# schematics.net
KiCad netlist of a schematic drawn in Altium Designer
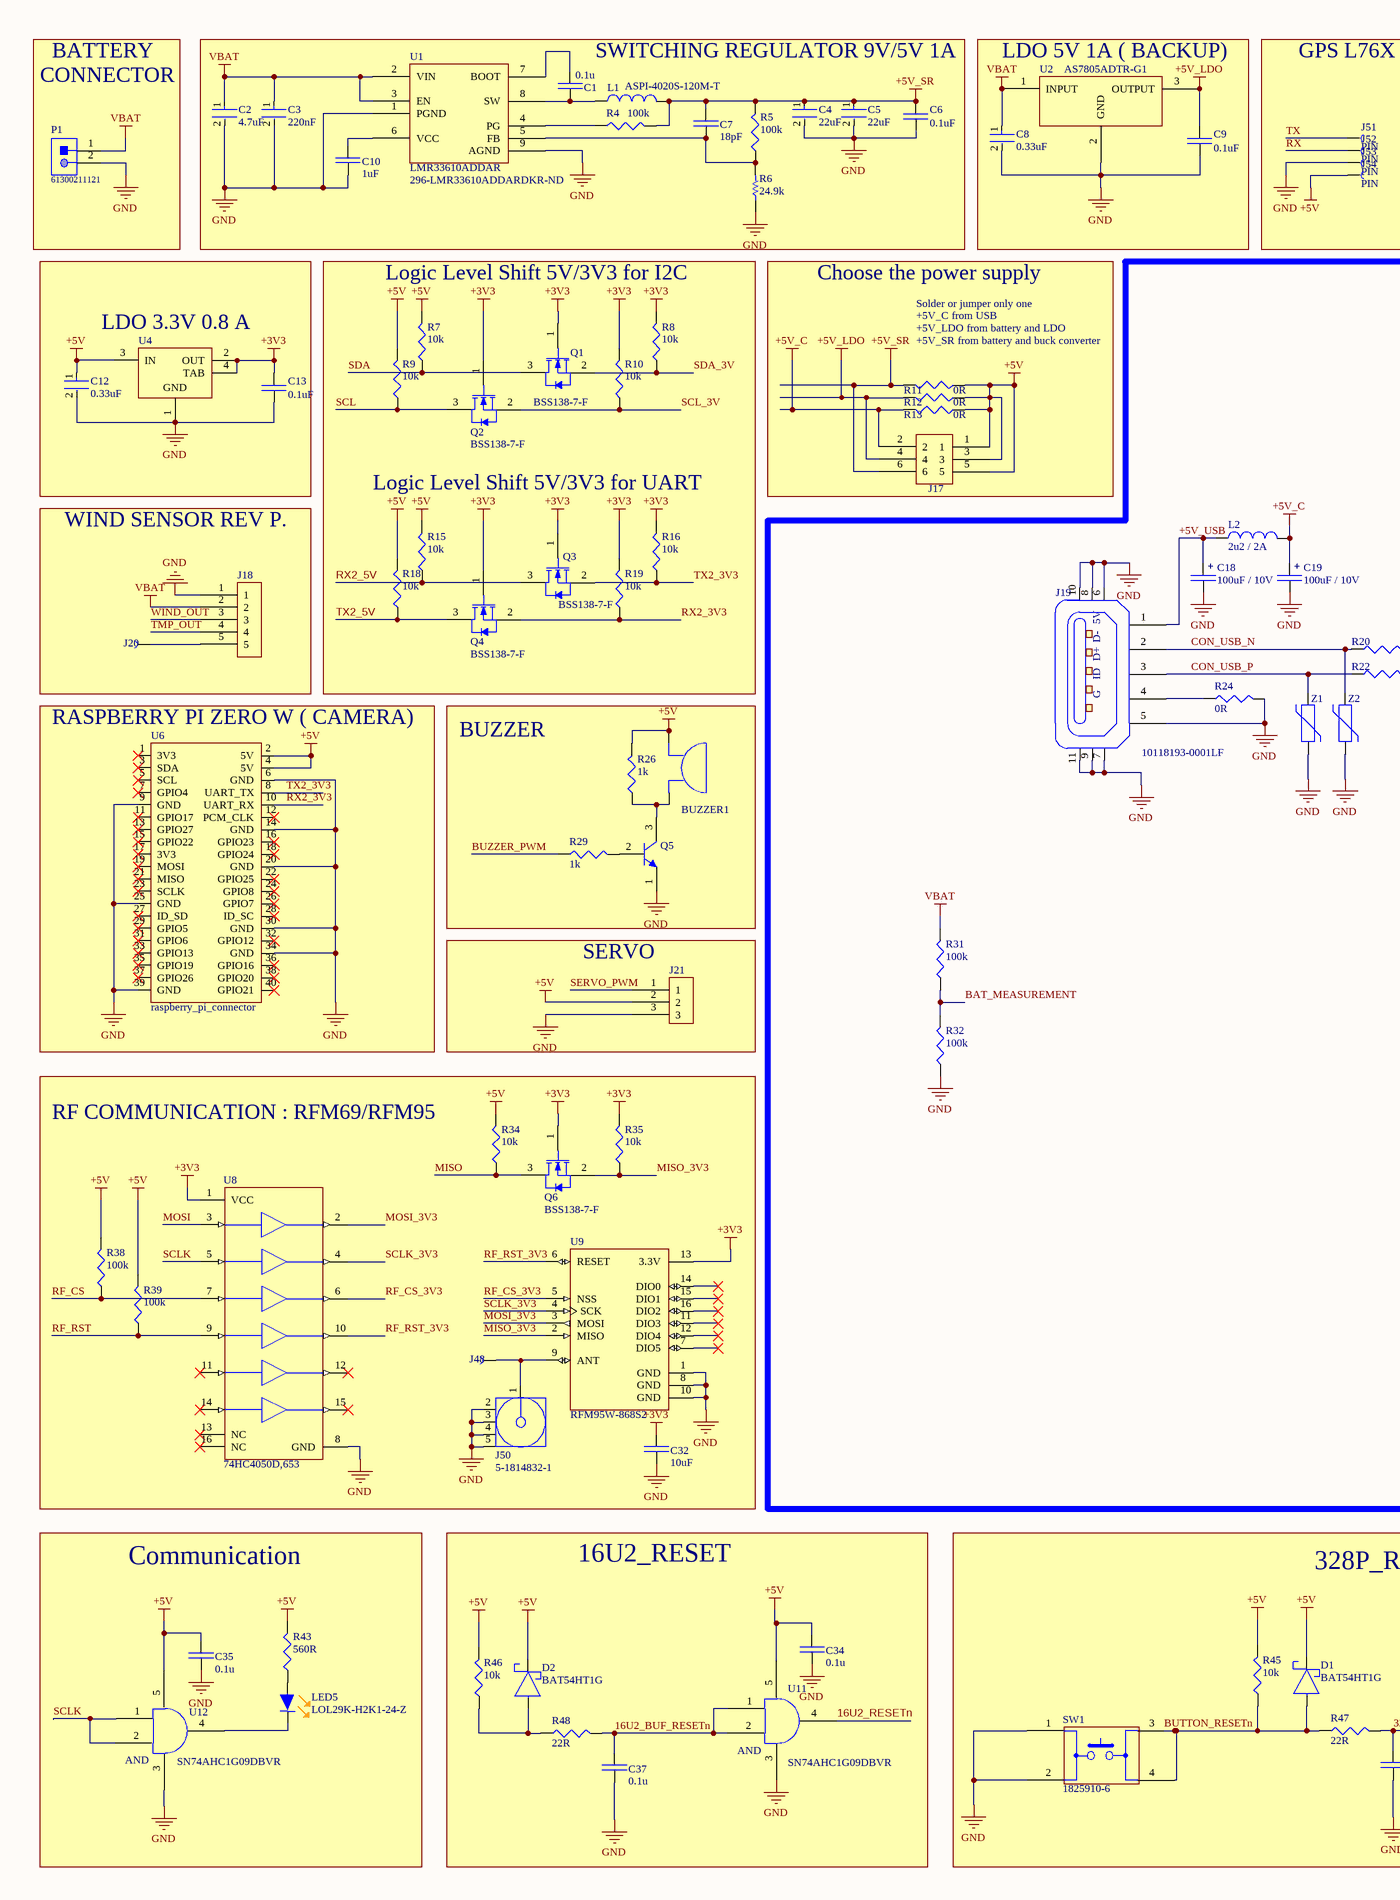
[diagram p0: schematics.SchDoc, left]
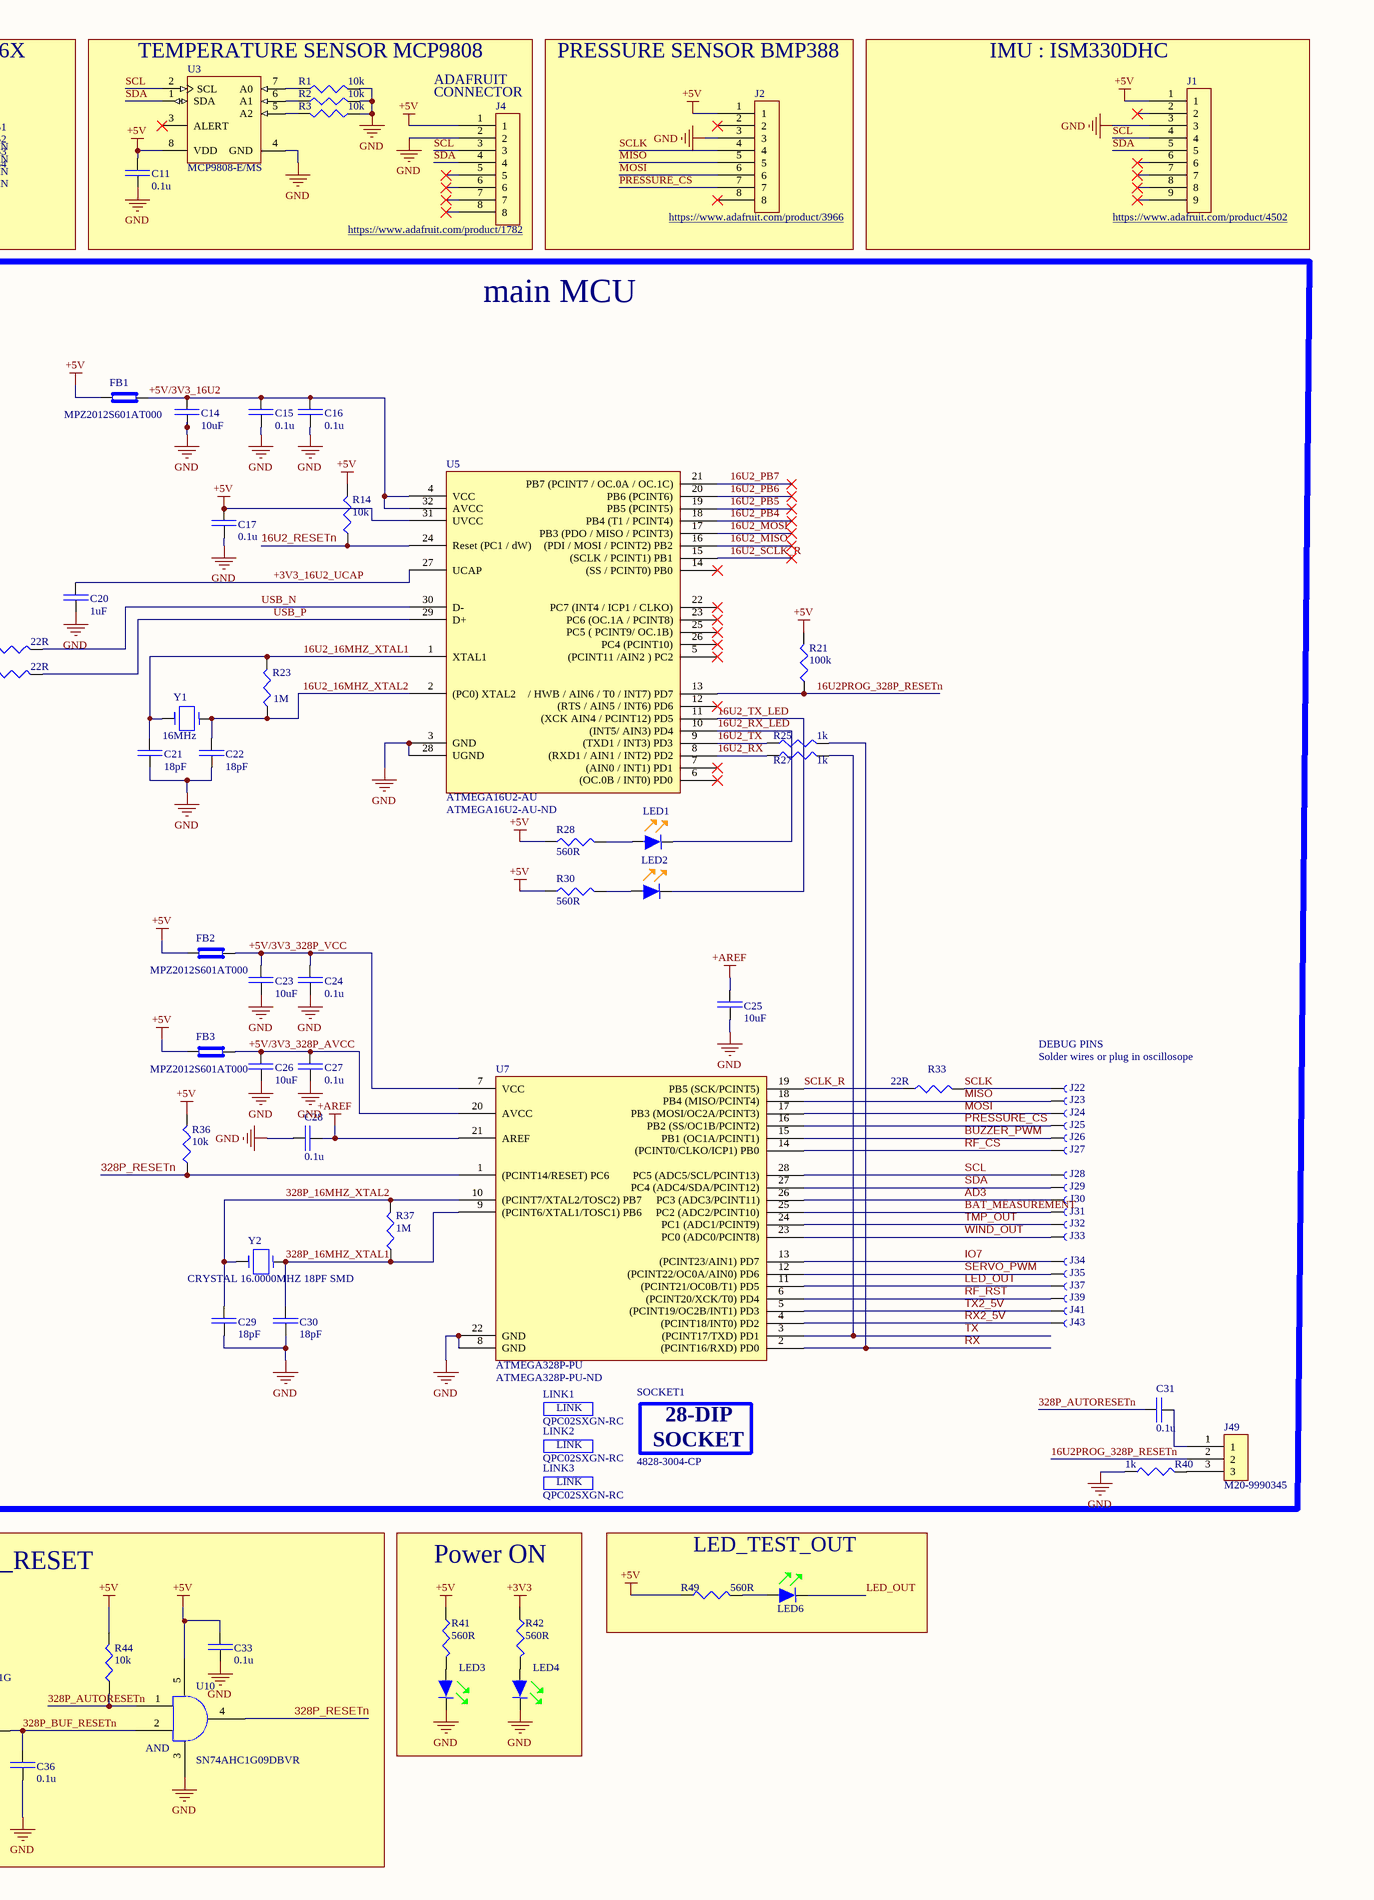
[diagram p1: schematics.SchDoc, right]

(export (version "E")
  (design (tool "Eeschema 10.0.6"))
  (components
    (comp (ref "BUZZER1")
      (value "PS1420P02CT")
      (footprint "PS1420P02CT")
      (description "AUDIO PIEZO TRANSDUCER 30V TH")
      (fields (field (name "MANUFACTURER") "TDK"))
      (libsource (lib "sch_library") (part "PS1420P02CT"))
    )
    (comp (ref "C1")
      (value "0.1u")
      (footprint "CAP_603")
      (description "CL10 Series 0603 0.1 uF 50 V ±10% Tolerance X7R Multilayer Ceramic Capacitor")
      (fields
        (field (name "MANUFACTURER") "Samsung")
        (field (name "MANUFACTURER PART NUMBER") "CL10B104KB8NNNL")
      )
      (libsource (lib "sch_library") (part "CL10B104KB8NNNL"))
    )
    (comp (ref "C2")
      (value "4.7uF")
      (footprint "FP-CL21-IPC_B")
      (description "CL21 Series 0805 4.7uF 25V ±10% Tolerance X5R Multilayer Ceramic Chip Capacitor")
      (fields (field (name "TOLERANCE") "10%") (field (name "VOLTAGE") "25V"))
      (libsource (lib "Altium Content Vault") (part "b4654b650e69147ec39a6b967a45e02"))
    )
    (comp (ref "C3")
      (value "220nF")
      (footprint "FP-CC0603-DA-MFG")
      (description "0603 0.22 uF 16 V ±10 % Tolerance X7R SMT Multilayer Ceramic Capacitor")
      (fields
        (field (name "MANUFACTURER") "YAGEO")
        (field (name "OCTOPART") "https://octopart.com/cc0603krx7r7bb224-yageo-6827757")
      )
      (libsource (lib "Altium Content Vault") (part "11868f565c42a9108669ba33697ecf6"))
    )
    (comp (ref "C4")
      (value "22uF")
      (footprint "FP-CL31-IPC_A")
      (description "Cap Ceramic 22uF 16V X5R ±20% SMD 1206 +85°C Embossed T/R")
      (fields (field (name "TOLERANCE") "20%") (field (name "VOLTAGE") "16V"))
      (libsource (lib "Altium Content Vault") (part "b4654b650e69147ec39a6b967a45e02"))
    )
    (comp (ref "C5")
      (value "22uF")
      (footprint "FP-CL31-IPC_A")
      (description "Cap Ceramic 22uF 16V X5R ±20% SMD 1206 +85°C Embossed T/R")
      (fields (field (name "TOLERANCE") "20%") (field (name "VOLTAGE") "16V"))
      (libsource (lib "Altium Content Vault") (part "b4654b650e69147ec39a6b967a45e02"))
    )
    (comp (ref "C6")
      (value "0.1uF")
      (footprint "CAP_603")
      (description "CL10 Series 0603 0.1 uF 50 V ±10% Tolerance X7R Multilayer Ceramic Capacitor")
      (fields
        (field (name "MANUFACTURER") "Samsung")
        (field (name "MANUFACTURER PART NUMBER") "CL10B104KB8NNNL")
      )
      (libsource (lib "sch_library") (part "CL10B104KB8NNNL"))
    )
    (comp (ref "C7")
      (value "18pF")
      (footprint "CAP_603")
      (description "0603 18 pF 50V ±5% Tolerance C0G/NP0 Surface Mount Multilayer Ceramic Capacitor")
      (fields
        (field (name "MANUFACTURER") "Kyocera AVX")
        (field (name "MANUFACTURER PART NUMBER") "06035A180JAT2A")
      )
      (libsource (lib "sch_library") (part "06035A180JAT2A"))
    )
    (comp (ref "C8")
      (value "0.33uF")
      (footprint "FP-CL21-F-IPC_C")
      (description "CAP CER 0.33UF 50V X7R 0805")
      (fields
        (field (name "MANUFACTURER") "Samsung Electro-Mechanics")
        (field (name "OCTOPART") "https://octopart.com/cl21b334kbfnnne-samsung-9287149")
      )
      (libsource (lib "Altium Content Vault") (part "11868f565c42a9108669ba33697ecf6"))
    )
    (comp (ref "C9")
      (value "0.1uF")
      (footprint "CAP_603")
      (description "CL10 Series 0603 0.1 uF 50 V ±10% Tolerance X7R Multilayer Ceramic Capacitor")
      (fields
        (field (name "MANUFACTURER") "Samsung")
        (field (name "MANUFACTURER PART NUMBER") "CL10B104KB8NNNL")
      )
      (libsource (lib "sch_library") (part "CL10B104KB8NNNL"))
    )
    (comp (ref "C10")
      (value "1uF")
      (footprint "CAP_603")
      (fields
        (field (name "MANUFACTURER") "Yageo")
        (field (name "MANUFACTURER PART NUMBER") "CC0603KRX5R8BB105")
        (field (name "TOLERANCE") "10%")
      )
      (libsource (lib "sch_library") (part "CC0603KRX5R8BB105"))
    )
    (comp (ref "C11")
      (value "0.1u")
      (footprint "CAP_603")
      (description "CL10 Series 0603 0.1 uF 50 V ±10% Tolerance X7R Multilayer Ceramic Capacitor")
      (fields
        (field (name "MANUFACTURER") "Samsung")
        (field (name "MANUFACTURER PART NUMBER") "CL10B104KB8NNNL")
      )
      (libsource (lib "sch_library") (part "CL10B104KB8NNNL"))
    )
    (comp (ref "C12")
      (value "0.33uF")
      (footprint "FP-CL21-F-IPC_C")
      (description "CAP CER 0.33UF 50V X7R 0805")
      (fields
        (field (name "MANUFACTURER") "Samsung Electro-Mechanics")
        (field (name "OCTOPART") "https://octopart.com/cl21b334kbfnnne-samsung-9287149")
      )
      (libsource (lib "Altium Content Vault") (part "11868f565c42a9108669ba33697ecf6"))
    )
    (comp (ref "C13")
      (value "0.1uF")
      (footprint "CAP_603")
      (description "CL10 Series 0603 0.1 uF 50 V ±10% Tolerance X7R Multilayer Ceramic Capacitor")
      (fields
        (field (name "MANUFACTURER") "Samsung")
        (field (name "MANUFACTURER PART NUMBER") "CL10B104KB8NNNL")
      )
      (libsource (lib "sch_library") (part "CL10B104KB8NNNL"))
    )
    (comp (ref "C14")
      (value "10uF")
      (footprint "CAP_0805")
      (description "Ceramic capacitor SMD 0805 10 µF 16 V 10 %")
      (fields
        (field (name "MANUFACTURER") "Samsung")
        (field (name "MANUFACTURER PART NUMBER") "CL21A106KOQNNNG")
      )
      (libsource (lib "sch_library") (part "CL21A106KOQNNNG"))
    )
    (comp (ref "C15")
      (value "0.1u")
      (footprint "CAP_603")
      (description "CL10 Series 0603 0.1 uF 50 V ±10% Tolerance X7R Multilayer Ceramic Capacitor")
      (fields
        (field (name "MANUFACTURER") "Samsung")
        (field (name "MANUFACTURER PART NUMBER") "CL10B104KB8NNNL")
      )
      (libsource (lib "sch_library") (part "CL10B104KB8NNNL"))
    )
    (comp (ref "C16")
      (value "0.1u")
      (footprint "CAP_603")
      (description "CL10 Series 0603 0.1 uF 50 V ±10% Tolerance X7R Multilayer Ceramic Capacitor")
      (fields
        (field (name "MANUFACTURER") "Samsung")
        (field (name "MANUFACTURER PART NUMBER") "CL10B104KB8NNNL")
      )
      (libsource (lib "sch_library") (part "CL10B104KB8NNNL"))
    )
    (comp (ref "C17")
      (value "0.1u")
      (footprint "CAP_603")
      (description "CL10 Series 0603 0.1 uF 50 V ±10% Tolerance X7R Multilayer Ceramic Capacitor")
      (fields
        (field (name "MANUFACTURER") "Samsung")
        (field (name "MANUFACTURER PART NUMBER") "CL10B104KB8NNNL")
      )
      (libsource (lib "sch_library") (part "CL10B104KB8NNNL"))
    )
    (comp (ref "C18")
      (value "100uF / 10V")
      (footprint "EEE-1AA101WR")
      (description "Cap Aluminum 100uF 10V 20% (5 X 5.4mm) SMD 50mA 1000 hr 85°C T/R")
      (fields
        (field (name "MANUFACTURER") "Panasonic")
        (field (name "MANUFACTURER PART NUMBER") "EEE-1AA101WR")
      )
      (libsource (lib "sch_library") (part "EEE-1AA101WR"))
    )
    (comp (ref "C19")
      (value "100uF / 10V")
      (footprint "EEE-1AA101WR")
      (description "Cap Aluminum 100uF 10V 20% (5 X 5.4mm) SMD 50mA 1000 hr 85°C T/R")
      (fields
        (field (name "MANUFACTURER") "Panasonic")
        (field (name "MANUFACTURER PART NUMBER") "EEE-1AA101WR")
      )
      (libsource (lib "sch_library") (part "EEE-1AA101WR"))
    )
    (comp (ref "C20")
      (value "1uF")
      (footprint "CAP_603")
      (fields
        (field (name "MANUFACTURER") "Yageo")
        (field (name "MANUFACTURER PART NUMBER") "CC0603KRX5R8BB105")
        (field (name "TOLERANCE") "10%")
      )
      (libsource (lib "sch_library") (part "CC0603KRX5R8BB105"))
    )
    (comp (ref "C21")
      (value "18pF")
      (footprint "CAP_603")
      (description "0603 18 pF 50V ±5% Tolerance C0G/NP0 Surface Mount Multilayer Ceramic Capacitor")
      (fields
        (field (name "MANUFACTURER") "Kyocera AVX")
        (field (name "MANUFACTURER PART NUMBER") "06035A180JAT2A")
      )
      (libsource (lib "sch_library") (part "06035A180JAT2A"))
    )
    (comp (ref "C22")
      (value "18pF")
      (footprint "CAP_603")
      (description "0603 18 pF 50V ±5% Tolerance C0G/NP0 Surface Mount Multilayer Ceramic Capacitor")
      (fields
        (field (name "MANUFACTURER") "Kyocera AVX")
        (field (name "MANUFACTURER PART NUMBER") "06035A180JAT2A")
      )
      (libsource (lib "sch_library") (part "06035A180JAT2A"))
    )
    (comp (ref "C23")
      (value "10uF")
      (footprint "CAP_0805")
      (description "Ceramic capacitor SMD 0805 10 µF 16 V 10 %")
      (fields
        (field (name "MANUFACTURER") "Samsung")
        (field (name "MANUFACTURER PART NUMBER") "CL21A106KOQNNNG")
      )
      (libsource (lib "sch_library") (part "CL21A106KOQNNNG"))
    )
    (comp (ref "C24")
      (value "0.1u")
      (footprint "CAP_603")
      (description "CL10 Series 0603 0.1 uF 50 V ±10% Tolerance X7R Multilayer Ceramic Capacitor")
      (fields
        (field (name "MANUFACTURER") "Samsung")
        (field (name "MANUFACTURER PART NUMBER") "CL10B104KB8NNNL")
      )
      (libsource (lib "sch_library") (part "CL10B104KB8NNNL"))
    )
    (comp (ref "C25")
      (value "10uF")
      (footprint "CAP_0805")
      (description "Ceramic capacitor SMD 0805 10 µF 16 V 10 %")
      (fields
        (field (name "MANUFACTURER") "Samsung")
        (field (name "MANUFACTURER PART NUMBER") "CL21A106KOQNNNG")
      )
      (libsource (lib "sch_library") (part "CL21A106KOQNNNG"))
    )
    (comp (ref "C26")
      (value "10uF")
      (footprint "CAP_0805")
      (description "Ceramic capacitor SMD 0805 10 µF 16 V 10 %")
      (fields
        (field (name "MANUFACTURER") "Samsung")
        (field (name "MANUFACTURER PART NUMBER") "CL21A106KOQNNNG")
      )
      (libsource (lib "sch_library") (part "CL21A106KOQNNNG"))
    )
    (comp (ref "C27")
      (value "0.1u")
      (footprint "CAP_603")
      (description "CL10 Series 0603 0.1 uF 50 V ±10% Tolerance X7R Multilayer Ceramic Capacitor")
      (fields
        (field (name "MANUFACTURER") "Samsung")
        (field (name "MANUFACTURER PART NUMBER") "CL10B104KB8NNNL")
      )
      (libsource (lib "sch_library") (part "CL10B104KB8NNNL"))
    )
    (comp (ref "C28")
      (value "0.1u")
      (footprint "CAP_603")
      (description "CL10 Series 0603 0.1 uF 50 V ±10% Tolerance X7R Multilayer Ceramic Capacitor")
      (fields
        (field (name "MANUFACTURER") "Samsung")
        (field (name "MANUFACTURER PART NUMBER") "CL10B104KB8NNNL")
      )
      (libsource (lib "sch_library") (part "CL10B104KB8NNNL"))
    )
    (comp (ref "C29")
      (value "18pF")
      (footprint "CAP_603")
      (description "0603 18 pF 50V ±5% Tolerance C0G/NP0 Surface Mount Multilayer Ceramic Capacitor")
      (fields
        (field (name "MANUFACTURER") "Kyocera AVX")
        (field (name "MANUFACTURER PART NUMBER") "06035A180JAT2A")
      )
      (libsource (lib "sch_library") (part "06035A180JAT2A"))
    )
    (comp (ref "C30")
      (value "18pF")
      (footprint "CAP_603")
      (description "0603 18 pF 50V ±5% Tolerance C0G/NP0 Surface Mount Multilayer Ceramic Capacitor")
      (fields
        (field (name "MANUFACTURER") "Kyocera AVX")
        (field (name "MANUFACTURER PART NUMBER") "06035A180JAT2A")
      )
      (libsource (lib "sch_library") (part "06035A180JAT2A"))
    )
    (comp (ref "C31")
      (value "0.1u")
      (footprint "CAP_603")
      (description "CL10 Series 0603 0.1 uF 50 V ±10% Tolerance X7R Multilayer Ceramic Capacitor")
      (fields
        (field (name "MANUFACTURER") "Samsung")
        (field (name "MANUFACTURER PART NUMBER") "CL10B104KB8NNNL")
      )
      (libsource (lib "sch_library") (part "CL10B104KB8NNNL"))
    )
    (comp (ref "C32")
      (value "10uF")
      (footprint "CAP_0805")
      (description "Ceramic capacitor SMD 0805 10 µF 16 V 10 %")
      (fields
        (field (name "MANUFACTURER") "Samsung")
        (field (name "MANUFACTURER PART NUMBER") "CL21A106KOQNNNG")
      )
      (libsource (lib "sch_library") (part "CL21A106KOQNNNG"))
    )
    (comp (ref "C33")
      (value "0.1u")
      (footprint "CAP_603")
      (description "CL10 Series 0603 0.1 uF 50 V ±10% Tolerance X7R Multilayer Ceramic Capacitor")
      (fields
        (field (name "MANUFACTURER") "Samsung")
        (field (name "MANUFACTURER PART NUMBER") "CL10B104KB8NNNL")
      )
      (libsource (lib "sch_library") (part "CL10B104KB8NNNL"))
    )
    (comp (ref "C34")
      (value "0.1u")
      (footprint "CAP_603")
      (description "CL10 Series 0603 0.1 uF 50 V ±10% Tolerance X7R Multilayer Ceramic Capacitor")
      (fields
        (field (name "MANUFACTURER") "Samsung")
        (field (name "MANUFACTURER PART NUMBER") "CL10B104KB8NNNL")
      )
      (libsource (lib "sch_library") (part "CL10B104KB8NNNL"))
    )
    (comp (ref "C35")
      (value "0.1u")
      (footprint "CAP_603")
      (description "CL10 Series 0603 0.1 uF 50 V ±10% Tolerance X7R Multilayer Ceramic Capacitor")
      (fields
        (field (name "MANUFACTURER") "Samsung")
        (field (name "MANUFACTURER PART NUMBER") "CL10B104KB8NNNL")
      )
      (libsource (lib "sch_library") (part "CL10B104KB8NNNL"))
    )
    (comp (ref "C36")
      (value "0.1u")
      (footprint "CAP_603")
      (description "CL10 Series 0603 0.1 uF 50 V ±10% Tolerance X7R Multilayer Ceramic Capacitor")
      (fields
        (field (name "MANUFACTURER") "Samsung")
        (field (name "MANUFACTURER PART NUMBER") "CL10B104KB8NNNL")
      )
      (libsource (lib "sch_library") (part "CL10B104KB8NNNL"))
    )
    (comp (ref "C37")
      (value "0.1u")
      (footprint "CAP_603")
      (description "CL10 Series 0603 0.1 uF 50 V ±10% Tolerance X7R Multilayer Ceramic Capacitor")
      (fields
        (field (name "MANUFACTURER") "Samsung")
        (field (name "MANUFACTURER PART NUMBER") "CL10B104KB8NNNL")
      )
      (libsource (lib "sch_library") (part "CL10B104KB8NNNL"))
    )
    (comp (ref "D1")
      (value "BAT54HT1G")
      (footprint "BAT54HT1G")
      (description "Small Signal Schottky Diode, Single, 30 V, 200 mA, 800 mV, 600 mA, 150 C ;RoHS Compliant: Yes")
      (fields (field (name "MANUFACTURER") "ON Semiconductor / Fairchild"))
      (libsource (lib "sch_library") (part "BAT54HT1G"))
    )
    (comp (ref "D2")
      (value "BAT54HT1G")
      (footprint "BAT54HT1G")
      (description "Small Signal Schottky Diode, Single, 30 V, 200 mA, 800 mV, 600 mA, 150 C ;RoHS Compliant: Yes")
      (fields (field (name "MANUFACTURER") "ON Semiconductor / Fairchild"))
      (libsource (lib "sch_library") (part "BAT54HT1G"))
    )
    (comp (ref "FB1")
      (value "MPZ2012S601AT000")
      (footprint "FB_0805")
      (description "FERRITE BEAD 600 OHM 0805 1LN")
      (fields (field (name "MANUFACTURER") "TDK"))
      (libsource (lib "sch_library") (part "MPZ2012S601AT000"))
    )
    (comp (ref "FB2")
      (value "MPZ2012S601AT000")
      (footprint "FB_0805")
      (description "FERRITE BEAD 600 OHM 0805 1LN")
      (fields (field (name "MANUFACTURER") "TDK"))
      (libsource (lib "sch_library") (part "MPZ2012S601AT000"))
    )
    (comp (ref "FB3")
      (value "MPZ2012S601AT000")
      (footprint "FB_0805")
      (description "FERRITE BEAD 600 OHM 0805 1LN")
      (fields (field (name "MANUFACTURER") "TDK"))
      (libsource (lib "sch_library") (part "MPZ2012S601AT000"))
    )
    (comp (ref "J1")
      (value "https://www.adafruit.com/product/4502")
      (footprint "ISM330DHCX_adafruit")
      (description "https://www.adafruit.com/product/4502#technical-details")
      (libsource (lib "sch_library") (part "ISM330DHCX_adafruit"))
    )
    (comp (ref "J2")
      (value "https://www.adafruit.com/product/3966")
      (footprint "BMP388_adafruit")
      (fields (field (name "MANUFACTURER") "Harwin") (field (name "MANUFACTURER PART NUMBER") "M20-7820842"))
      (libsource (lib "sch_library") (part "BMP388_adafruit"))
    )
    (comp (ref "J4")
      (value "https://www.adafruit.com/product/1782")
      (footprint "MCP9808_adafruit")
      (libsource (lib "sch_library") (part "MCP9808_adafruit"))
    )
    (comp (ref "J17")
      (value "M20-9760346")
      (footprint "HEADER_MALE_2x3PIN")
      (description "03+03 DIL VERT PIN HDR")
      (fields (field (name "MANUFACTURER") "Harwin"))
      (libsource (lib "sch_library") (part "M20-9760346"))
    )
    (comp (ref "J18")
      (value "M20-9990546 (3)")
      (footprint "HEADER_MALE_1X5")
      (description "HEADER, 1ROW, 5WAY")
      (fields (field (name "MANUFACTURER") "Harwin") (field (name "MANUFACTURER PART NUMBER") "M20-9990546"))
      (libsource (lib "sch_library") (part "M20-9990546 (3)"))
    )
    (comp (ref "J19")
      (value "10118193-0001LF")
      (footprint "10118193-0001LF")
      (description "CONN USB MICRO B RECPT SMT R/A")
      (fields (field (name "MANUFACTURER") "Amphenol FCI"))
      (libsource (lib "sch_library") (part "10118193-0001LF"))
    )
    (comp (ref "J20") (value "PIN") (footprint "PIN") (libsource (lib "sch_library") (part "PIN")))
    (comp (ref "J21")
      (value "M20-9990345")
      (footprint "HEADER_MALE_1x3")
      (fields (field (name "MANUFACTURER") "Harwin"))
      (libsource (lib "sch_library") (part "M20-9990345"))
    )
    (comp (ref "J22") (value "PIN") (footprint "PIN") (libsource (lib "sch_library") (part "PIN")))
    (comp (ref "J23") (value "PIN") (footprint "PIN") (libsource (lib "sch_library") (part "PIN")))
    (comp (ref "J24") (value "PIN") (footprint "PIN") (libsource (lib "sch_library") (part "PIN")))
    (comp (ref "J25") (value "PIN") (footprint "PIN") (libsource (lib "sch_library") (part "PIN")))
    (comp (ref "J26") (value "PIN") (footprint "PIN") (libsource (lib "sch_library") (part "PIN")))
    (comp (ref "J27") (value "PIN") (footprint "PIN") (libsource (lib "sch_library") (part "PIN")))
    (comp (ref "J28") (value "PIN") (footprint "PIN") (libsource (lib "sch_library") (part "PIN")))
    (comp (ref "J29") (value "PIN") (footprint "PIN") (libsource (lib "sch_library") (part "PIN")))
    (comp (ref "J30") (value "PIN") (footprint "PIN") (libsource (lib "sch_library") (part "PIN")))
    (comp (ref "J31") (value "PIN") (footprint "PIN") (libsource (lib "sch_library") (part "PIN")))
    (comp (ref "J32") (value "PIN") (footprint "PIN") (libsource (lib "sch_library") (part "PIN")))
    (comp (ref "J33") (value "PIN") (footprint "PIN") (libsource (lib "sch_library") (part "PIN")))
    (comp (ref "J34") (value "PIN") (footprint "PIN") (libsource (lib "sch_library") (part "PIN")))
    (comp (ref "J35") (value "PIN") (footprint "PIN") (libsource (lib "sch_library") (part "PIN")))
    (comp (ref "J37") (value "PIN") (footprint "PIN") (libsource (lib "sch_library") (part "PIN")))
    (comp (ref "J39") (value "PIN") (footprint "PIN") (libsource (lib "sch_library") (part "PIN")))
    (comp (ref "J41") (value "PIN") (footprint "PIN") (libsource (lib "sch_library") (part "PIN")))
    (comp (ref "J43") (value "PIN") (footprint "PIN") (libsource (lib "sch_library") (part "PIN")))
    (comp (ref "J48") (value "PIN") (footprint "PIN") (libsource (lib "sch_library") (part "PIN")))
    (comp (ref "J49")
      (value "M20-9990345")
      (footprint "HEADER_MALE_1x3")
      (fields (field (name "MANUFACTURER") "Harwin"))
      (libsource (lib "sch_library") (part "M20-9990345"))
    )
    (comp (ref "J50")
      (value "5-1814832-1")
      (footprint "TECO-5-1814832-1_V")
      (fields (field (name "MANUFACTURER") "TE Connectivity"))
      (libsource (lib "Altium Content Vault") (part "CN-S-4F-RF5"))
    )
    (comp (ref "J51") (value "PIN") (footprint "PIN") (libsource (lib "sch_library") (part "PIN")))
    (comp (ref "J52") (value "PIN") (footprint "PIN") (libsource (lib "sch_library") (part "PIN")))
    (comp (ref "J53") (value "PIN") (footprint "PIN") (libsource (lib "sch_library") (part "PIN")))
    (comp (ref "J54") (value "PIN") (footprint "PIN") (libsource (lib "sch_library") (part "PIN")))
    (comp (ref "L1")
      (value "ASPI-4020S-120M-T")
      (footprint "ASPI-4020S")
      (description "Ind Power Shielded Wirewound 12uH 20% 100KHz Ferrite 880mA 1616 T/R")
      (fields (field (name "MANUFACTURER") "Abracon") (field (name "TOLERANCE") "20%"))
      (libsource (lib "sch_library") (part "ASPI-4020S-120M-T"))
    )
    (comp (ref "L2")
      (value "2u2 / 2A")
      (footprint "L_1210")
      (description "FIXED IND 2.2UH 2A 80 MOHM SMD")
      (fields
        (field (name "MANUFACTURER") "KEMET")
        (field (name "MANUFACTURER PART NUMBER") "L1210R2R2MDWIT")
      )
      (libsource (lib "sch_library") (part "L1210R2R2MDWIT"))
    )
    (comp (ref "LED1")
      (value "LOL29K-H2K1-24-Z")
      (footprint "LED_0603")
      (description "OSRAM - LO L29K-H2K1-24-Z - SMARTLED 0603 ORANGE")
      (fields (field (name "MANUFACTURER") "Osram Opto"))
      (libsource (lib "sch_library") (part "LOL29K-H2K1-24-Z"))
    )
    (comp (ref "LED2")
      (value "LOL29K-H2K1-24-Z")
      (footprint "LED_0603")
      (description "OSRAM - LO L29K-H2K1-24-Z - SMARTLED 0603 ORANGE")
      (fields (field (name "MANUFACTURER") "Osram Opto"))
      (libsource (lib "sch_library") (part "LOL29K-H2K1-24-Z"))
    )
    (comp (ref "LED3")
      (value "LGL29K-F2J1-24-Z")
      (footprint "LED_0603")
      (description "LED Uni-Color Green 572nm Automotive 2-Pin Chip 0603(1608Metric) T/R")
      (fields (field (name "MANUFACTURER") "Osram Opto"))
      (libsource (lib "sch_library") (part "LGL29K-F2J1-24-Z"))
    )
    (comp (ref "LED4")
      (value "LGL29K-F2J1-24-Z")
      (footprint "LED_0603")
      (description "LED Uni-Color Green 572nm Automotive 2-Pin Chip 0603(1608Metric) T/R")
      (fields (field (name "MANUFACTURER") "Osram Opto"))
      (libsource (lib "sch_library") (part "LGL29K-F2J1-24-Z"))
    )
    (comp (ref "LED5")
      (value "LOL29K-H2K1-24-Z")
      (footprint "LED_0603")
      (description "OSRAM - LO L29K-H2K1-24-Z - SMARTLED 0603 ORANGE")
      (fields (field (name "MANUFACTURER") "Osram Opto"))
      (libsource (lib "sch_library") (part "LOL29K-H2K1-24-Z"))
    )
    (comp (ref "LED6")
      (value "LGL29K-F2J1-24-Z")
      (footprint "LED_0603")
      (description "LED Uni-Color Green 572nm Automotive 2-Pin Chip 0603(1608Metric) T/R")
      (fields (field (name "MANUFACTURER") "Osram Opto"))
      (libsource (lib "sch_library") (part "LGL29K-F2J1-24-Z"))
    )
    (comp (ref "LINK1")
      (value "QPC02SXGN-RC")
      (description "CONN JUMPER SHORTING .100\" GOLD")
      (fields (field (name "MANUFACTURER") "Sullins"))
      (libsource (lib "sch_library") (part "QPC02SXGN-RC"))
    )
    (comp (ref "LINK2")
      (value "QPC02SXGN-RC")
      (description "CONN JUMPER SHORTING .100\" GOLD")
      (fields (field (name "MANUFACTURER") "Sullins"))
      (libsource (lib "sch_library") (part "QPC02SXGN-RC"))
    )
    (comp (ref "LINK3")
      (value "QPC02SXGN-RC")
      (description "CONN JUMPER SHORTING .100\" GOLD")
      (fields (field (name "MANUFACTURER") "Sullins"))
      (libsource (lib "sch_library") (part "QPC02SXGN-RC"))
    )
    (comp (ref "P1")
      (value "61300211121")
      (footprint "61300211121")
      (description "THT Vertical Pin Header WR-PHD, Pitch 2.54 mm, Single Row, 2 pins")
      (fields (field (name "MANUFACTURER") "Wurth Elektronik") (field (name "PUBLISHER") "WurthElektronik"))
      (libsource (lib "Altium Content Vault") (part "WE-CN-1P-M-R2"))
    )
    (comp (ref "Q1")
      (value "BSS138-7-F")
      (footprint "DIOD-SOT23-3_V")
      (description "N-Channel Enhancement Mode Mosfet, 50 V, 0.2 A, -55 to 150 degC, 3-Pin SOT23, RoHS, Tape and Reel")
      (fields (field (name "MANUFACTURER") "Diodes Inc"))
      (libsource (lib "Altium Content Vault") (part "NEMOS-GSD-3"))
    )
    (comp (ref "Q2")
      (value "BSS138-7-F")
      (footprint "DIOD-SOT23-3_V")
      (description "N-Channel Enhancement Mode Mosfet, 50 V, 0.2 A, -55 to 150 degC, 3-Pin SOT23, RoHS, Tape and Reel")
      (fields (field (name "MANUFACTURER") "Diodes Inc"))
      (libsource (lib "Altium Content Vault") (part "NEMOS-GSD-3"))
    )
    (comp (ref "Q3")
      (value "BSS138-7-F")
      (footprint "DIOD-SOT23-3_V")
      (description "N-Channel Enhancement Mode Mosfet, 50 V, 0.2 A, -55 to 150 degC, 3-Pin SOT23, RoHS, Tape and Reel")
      (fields (field (name "MANUFACTURER") "Diodes Inc"))
      (libsource (lib "Altium Content Vault") (part "NEMOS-GSD-3"))
    )
    (comp (ref "Q4")
      (value "BSS138-7-F")
      (footprint "DIOD-SOT23-3_V")
      (description "N-Channel Enhancement Mode Mosfet, 50 V, 0.2 A, -55 to 150 degC, 3-Pin SOT23, RoHS, Tape and Reel")
      (fields (field (name "MANUFACTURER") "Diodes Inc"))
      (libsource (lib "Altium Content Vault") (part "NEMOS-GSD-3"))
    )
    (comp (ref "Q5")
      (value "2SC2412KT146R")
      (footprint "ROHM-SOT-346-3_V")
      (fields (field (name "MANUFACTURER") "Rohm"))
      (libsource (lib "Altium Content Vault") (part "BJT-NPN-EBC-3"))
    )
    (comp (ref "Q6")
      (value "BSS138-7-F")
      (footprint "DIOD-SOT23-3_V")
      (description "N-Channel Enhancement Mode Mosfet, 50 V, 0.2 A, -55 to 150 degC, 3-Pin SOT23, RoHS, Tape and Reel")
      (fields (field (name "MANUFACTURER") "Diodes Inc"))
      (libsource (lib "Altium Content Vault") (part "NEMOS-GSD-3"))
    )
    (comp (ref "R1")
      (value "10k")
      (footprint "R_0603")
      (description "RES SMD 10K OHM 1% 1/10W 0603")
      (fields
        (field (name "MANUFACTURER") "Yageo")
        (field (name "MANUFACTURER PART NUMBER") "AC0603FR-0710KL")
      )
      (libsource (lib "sch_library") (part "AC0603FR-0710KL"))
    )
    (comp (ref "R2")
      (value "10k")
      (footprint "R_0603")
      (description "RES SMD 10K OHM 1% 1/10W 0603")
      (fields
        (field (name "MANUFACTURER") "Yageo")
        (field (name "MANUFACTURER PART NUMBER") "AC0603FR-0710KL")
      )
      (libsource (lib "sch_library") (part "AC0603FR-0710KL"))
    )
    (comp (ref "R3")
      (value "10k")
      (footprint "R_0603")
      (description "RES SMD 10K OHM 1% 1/10W 0603")
      (fields
        (field (name "MANUFACTURER") "Yageo")
        (field (name "MANUFACTURER PART NUMBER") "AC0603FR-0710KL")
      )
      (libsource (lib "sch_library") (part "AC0603FR-0710KL"))
    )
    (comp (ref "R4")
      (value "100k")
      (footprint "R_0603")
      (description "Res Thick Film 1.6 x 0.8 mm 100K Ohm 1% 0.1W(1/10W) 100ppm/ C Molded SMD Paper T/R")
      (fields
        (field (name "MANUFACTURER") "Yageo")
        (field (name "MANUFACTURER PART NUMBER") "RC0603FR-07100KL")
      )
      (libsource (lib "sch_library") (part "RC0603FR-07100KL"))
    )
    (comp (ref "R5")
      (value "100k")
      (footprint "R_0603")
      (description "Res Thick Film 1.6 x 0.8 mm 100K Ohm 1% 0.1W(1/10W) 100ppm/ C Molded SMD Paper T/R")
      (fields
        (field (name "MANUFACTURER") "Yageo")
        (field (name "MANUFACTURER PART NUMBER") "RC0603FR-07100KL")
      )
      (libsource (lib "sch_library") (part "RC0603FR-07100KL"))
    )
    (comp (ref "R6")
      (value "24.9k")
      (footprint "RESC1608X55X30LL15T15")
      (fields (field (name "PART NUMBER") "ERJ-3EKF2492V") (field (name "MANUFACTURER") "Panasonic"))
      (libsource (lib "Altium Content Vault") (part "RES"))
    )
    (comp (ref "R7")
      (value "10k")
      (footprint "R_0603")
      (description "RES SMD 10K OHM 1% 1/10W 0603")
      (fields
        (field (name "MANUFACTURER") "Yageo")
        (field (name "MANUFACTURER PART NUMBER") "AC0603FR-0710KL")
      )
      (libsource (lib "sch_library") (part "AC0603FR-0710KL"))
    )
    (comp (ref "R8")
      (value "10k")
      (footprint "R_0603")
      (description "RES SMD 10K OHM 1% 1/10W 0603")
      (fields
        (field (name "MANUFACTURER") "Yageo")
        (field (name "MANUFACTURER PART NUMBER") "AC0603FR-0710KL")
      )
      (libsource (lib "sch_library") (part "AC0603FR-0710KL"))
    )
    (comp (ref "R9")
      (value "10k")
      (footprint "R_0603")
      (description "RES SMD 10K OHM 1% 1/10W 0603")
      (fields
        (field (name "MANUFACTURER") "Yageo")
        (field (name "MANUFACTURER PART NUMBER") "AC0603FR-0710KL")
      )
      (libsource (lib "sch_library") (part "AC0603FR-0710KL"))
    )
    (comp (ref "R10")
      (value "10k")
      (footprint "R_0603")
      (description "RES SMD 10K OHM 1% 1/10W 0603")
      (fields
        (field (name "MANUFACTURER") "Yageo")
        (field (name "MANUFACTURER PART NUMBER") "AC0603FR-0710KL")
      )
      (libsource (lib "sch_library") (part "AC0603FR-0710KL"))
    )
    (comp (ref "R11")
      (value "0R")
      (footprint "R_0603")
      (description "YAGEO - RC0603FR-070RL - RES, THICK FILM, 0R, 1%, 0.1W, 0603")
      (fields
        (field (name "MANUFACTURER") "Yageo")
        (field (name "MANUFACTURER PART NUMBER") "RC0603FR-070RL")
      )
      (libsource (lib "sch_library") (part "RC0603FR-070RL"))
    )
    (comp (ref "R12")
      (value "0R")
      (footprint "R_0603")
      (description "YAGEO - RC0603FR-070RL - RES, THICK FILM, 0R, 1%, 0.1W, 0603")
      (fields
        (field (name "MANUFACTURER") "Yageo")
        (field (name "MANUFACTURER PART NUMBER") "RC0603FR-070RL")
      )
      (libsource (lib "sch_library") (part "RC0603FR-070RL"))
    )
    (comp (ref "R13")
      (value "0R")
      (footprint "R_0603")
      (description "YAGEO - RC0603FR-070RL - RES, THICK FILM, 0R, 1%, 0.1W, 0603")
      (fields
        (field (name "MANUFACTURER") "Yageo")
        (field (name "MANUFACTURER PART NUMBER") "RC0603FR-070RL")
      )
      (libsource (lib "sch_library") (part "RC0603FR-070RL"))
    )
    (comp (ref "R14")
      (value "10k")
      (footprint "R_0603")
      (description "RES SMD 10K OHM 1% 1/10W 0603")
      (fields
        (field (name "MANUFACTURER") "Yageo")
        (field (name "MANUFACTURER PART NUMBER") "AC0603FR-0710KL")
      )
      (libsource (lib "sch_library") (part "AC0603FR-0710KL"))
    )
    (comp (ref "R15")
      (value "10k")
      (footprint "R_0603")
      (description "RES SMD 10K OHM 1% 1/10W 0603")
      (fields
        (field (name "MANUFACTURER") "Yageo")
        (field (name "MANUFACTURER PART NUMBER") "AC0603FR-0710KL")
      )
      (libsource (lib "sch_library") (part "AC0603FR-0710KL"))
    )
    (comp (ref "R16")
      (value "10k")
      (footprint "R_0603")
      (description "RES SMD 10K OHM 1% 1/10W 0603")
      (fields
        (field (name "MANUFACTURER") "Yageo")
        (field (name "MANUFACTURER PART NUMBER") "AC0603FR-0710KL")
      )
      (libsource (lib "sch_library") (part "AC0603FR-0710KL"))
    )
    (comp (ref "R18")
      (value "10k")
      (footprint "R_0603")
      (description "RES SMD 10K OHM 1% 1/10W 0603")
      (fields
        (field (name "MANUFACTURER") "Yageo")
        (field (name "MANUFACTURER PART NUMBER") "AC0603FR-0710KL")
      )
      (libsource (lib "sch_library") (part "AC0603FR-0710KL"))
    )
    (comp (ref "R19")
      (value "10k")
      (footprint "R_0603")
      (description "RES SMD 10K OHM 1% 1/10W 0603")
      (fields
        (field (name "MANUFACTURER") "Yageo")
        (field (name "MANUFACTURER PART NUMBER") "AC0603FR-0710KL")
      )
      (libsource (lib "sch_library") (part "AC0603FR-0710KL"))
    )
    (comp (ref "R20")
      (value "22R")
      (footprint "R_0805")
      (description "RES SMD 22 OHM 1% 1/8W 0805")
      (fields
        (field (name "MANUFACTURER") "Yageo")
        (field (name "MANUFACTURER PART NUMBER") "RC0805FR-0722RL")
      )
      (libsource (lib "sch_library") (part "RC0805FR-0722RL"))
    )
    (comp (ref "R21")
      (value "100k")
      (footprint "R_0603")
      (description "Res Thick Film 1.6 x 0.8 mm 100K Ohm 1% 0.1W(1/10W) 100ppm/ C Molded SMD Paper T/R")
      (fields
        (field (name "MANUFACTURER") "Yageo")
        (field (name "MANUFACTURER PART NUMBER") "RC0603FR-07100KL")
      )
      (libsource (lib "sch_library") (part "RC0603FR-07100KL"))
    )
    (comp (ref "R22")
      (value "22R")
      (footprint "R_0805")
      (description "RES SMD 22 OHM 1% 1/8W 0805")
      (fields
        (field (name "MANUFACTURER") "Yageo")
        (field (name "MANUFACTURER PART NUMBER") "RC0805FR-0722RL")
      )
      (libsource (lib "sch_library") (part "RC0805FR-0722RL"))
    )
    (comp (ref "R23")
      (value "1M")
      (footprint "R_0603")
      (description "Yageo RC Series Thick Film Surface Mount Resistor 0603 Case 1M 1% 0.1W 100ppm/C")
      (fields
        (field (name "MANUFACTURER") "Yageo")
        (field (name "MANUFACTURER PART NUMBER") "RC0603FR-071ML")
      )
      (libsource (lib "sch_library") (part "RC0603FR-071ML"))
    )
    (comp (ref "R24")
      (value "0R")
      (footprint "R_0603")
      (description "YAGEO - RC0603FR-070RL - RES, THICK FILM, 0R, 1%, 0.1W, 0603")
      (fields
        (field (name "MANUFACTURER") "Yageo")
        (field (name "MANUFACTURER PART NUMBER") "RC0603FR-070RL")
      )
      (libsource (lib "sch_library") (part "RC0603FR-070RL"))
    )
    (comp (ref "R25")
      (value "1k")
      (footprint "R_0603")
      (description "Res Thick Film 0603 1K Ohm 1% 0.1W(1/10W) ±100ppm/C Epoxy Pad SMD Automotive T/R")
      (fields
        (field (name "MANUFACTURER") "Yageo")
        (field (name "MANUFACTURER PART NUMBER") "AC0603FR-071KL")
      )
      (libsource (lib "sch_library") (part "AC0603FR-071KL"))
    )
    (comp (ref "R26")
      (value "1k")
      (footprint "R_0603")
      (description "Res Thick Film 0603 1K Ohm 1% 0.1W(1/10W) ±100ppm/C Epoxy Pad SMD Automotive T/R")
      (fields
        (field (name "MANUFACTURER") "Yageo")
        (field (name "MANUFACTURER PART NUMBER") "AC0603FR-071KL")
      )
      (libsource (lib "sch_library") (part "AC0603FR-071KL"))
    )
    (comp (ref "R27")
      (value "1k")
      (footprint "R_0603")
      (description "Res Thick Film 0603 1K Ohm 1% 0.1W(1/10W) ±100ppm/C Epoxy Pad SMD Automotive T/R")
      (fields
        (field (name "MANUFACTURER") "Yageo")
        (field (name "MANUFACTURER PART NUMBER") "AC0603FR-071KL")
      )
      (libsource (lib "sch_library") (part "AC0603FR-071KL"))
    )
    (comp (ref "R28")
      (value "560R")
      (footprint "R_0603")
      (fields
        (field (name "MANUFACTURER") "Yageo")
        (field (name "MANUFACTURER PART NUMBER") "RC0603FR-07560RL")
        (field (name "TOLERANCE") "1%")
      )
      (libsource (lib "sch_library") (part "560R"))
    )
    (comp (ref "R29")
      (value "1k")
      (footprint "R_0603")
      (description "Res Thick Film 0603 1K Ohm 1% 0.1W(1/10W) ±100ppm/C Epoxy Pad SMD Automotive T/R")
      (fields
        (field (name "MANUFACTURER") "Yageo")
        (field (name "MANUFACTURER PART NUMBER") "AC0603FR-071KL")
      )
      (libsource (lib "sch_library") (part "AC0603FR-071KL"))
    )
    (comp (ref "R30")
      (value "560R")
      (footprint "R_0603")
      (fields
        (field (name "MANUFACTURER") "Yageo")
        (field (name "MANUFACTURER PART NUMBER") "RC0603FR-07560RL")
        (field (name "TOLERANCE") "1%")
      )
      (libsource (lib "sch_library") (part "560R"))
    )
    (comp (ref "R31")
      (value "100k")
      (footprint "R_0603")
      (description "Res Thick Film 1.6 x 0.8 mm 100K Ohm 1% 0.1W(1/10W) 100ppm/ C Molded SMD Paper T/R")
      (fields
        (field (name "MANUFACTURER") "Yageo")
        (field (name "MANUFACTURER PART NUMBER") "RC0603FR-07100KL")
      )
      (libsource (lib "sch_library") (part "RC0603FR-07100KL"))
    )
    (comp (ref "R32")
      (value "100k")
      (footprint "R_0603")
      (description "Res Thick Film 1.6 x 0.8 mm 100K Ohm 1% 0.1W(1/10W) 100ppm/ C Molded SMD Paper T/R")
      (fields
        (field (name "MANUFACTURER") "Yageo")
        (field (name "MANUFACTURER PART NUMBER") "RC0603FR-07100KL")
      )
      (libsource (lib "sch_library") (part "RC0603FR-07100KL"))
    )
    (comp (ref "R33")
      (value "22R")
      (footprint "R_0805")
      (description "RES SMD 22 OHM 1% 1/8W 0805")
      (fields
        (field (name "MANUFACTURER") "Yageo")
        (field (name "MANUFACTURER PART NUMBER") "RC0805FR-0722RL")
      )
      (libsource (lib "sch_library") (part "RC0805FR-0722RL"))
    )
    (comp (ref "R34")
      (value "10k")
      (footprint "R_0603")
      (description "RES SMD 10K OHM 1% 1/10W 0603")
      (fields
        (field (name "MANUFACTURER") "Yageo")
        (field (name "MANUFACTURER PART NUMBER") "AC0603FR-0710KL")
      )
      (libsource (lib "sch_library") (part "AC0603FR-0710KL"))
    )
    (comp (ref "R35")
      (value "10k")
      (footprint "R_0603")
      (description "RES SMD 10K OHM 1% 1/10W 0603")
      (fields
        (field (name "MANUFACTURER") "Yageo")
        (field (name "MANUFACTURER PART NUMBER") "AC0603FR-0710KL")
      )
      (libsource (lib "sch_library") (part "AC0603FR-0710KL"))
    )
    (comp (ref "R36")
      (value "10k")
      (footprint "R_0603")
      (description "RES SMD 10K OHM 1% 1/10W 0603")
      (fields
        (field (name "MANUFACTURER") "Yageo")
        (field (name "MANUFACTURER PART NUMBER") "AC0603FR-0710KL")
      )
      (libsource (lib "sch_library") (part "AC0603FR-0710KL"))
    )
    (comp (ref "R37")
      (value "1M")
      (footprint "R_0603")
      (description "Yageo RC Series Thick Film Surface Mount Resistor 0603 Case 1M 1% 0.1W 100ppm/C")
      (fields
        (field (name "MANUFACTURER") "Yageo")
        (field (name "MANUFACTURER PART NUMBER") "RC0603FR-071ML")
      )
      (libsource (lib "sch_library") (part "RC0603FR-071ML"))
    )
    (comp (ref "R38")
      (value "100k")
      (footprint "R_0603")
      (description "Res Thick Film 1.6 x 0.8 mm 100K Ohm 1% 0.1W(1/10W) 100ppm/ C Molded SMD Paper T/R")
      (fields
        (field (name "MANUFACTURER") "Yageo")
        (field (name "MANUFACTURER PART NUMBER") "RC0603FR-07100KL")
      )
      (libsource (lib "sch_library") (part "RC0603FR-07100KL"))
    )
    (comp (ref "R39")
      (value "100k")
      (footprint "R_0603")
      (description "Res Thick Film 1.6 x 0.8 mm 100K Ohm 1% 0.1W(1/10W) 100ppm/ C Molded SMD Paper T/R")
      (fields
        (field (name "MANUFACTURER") "Yageo")
        (field (name "MANUFACTURER PART NUMBER") "RC0603FR-07100KL")
      )
      (libsource (lib "sch_library") (part "RC0603FR-07100KL"))
    )
    (comp (ref "R40")
      (value "1k")
      (footprint "R_0603")
      (description "Res Thick Film 0603 1K Ohm 1% 0.1W(1/10W) ±100ppm/C Epoxy Pad SMD Automotive T/R")
      (fields
        (field (name "MANUFACTURER") "Yageo")
        (field (name "MANUFACTURER PART NUMBER") "AC0603FR-071KL")
      )
      (libsource (lib "sch_library") (part "AC0603FR-071KL"))
    )
    (comp (ref "R41")
      (value "560R")
      (footprint "R_0603")
      (fields
        (field (name "MANUFACTURER") "Yageo")
        (field (name "MANUFACTURER PART NUMBER") "RC0603FR-07560RL")
        (field (name "TOLERANCE") "1%")
      )
      (libsource (lib "sch_library") (part "560R"))
    )
    (comp (ref "R42")
      (value "560R")
      (footprint "R_0603")
      (fields
        (field (name "MANUFACTURER") "Yageo")
        (field (name "MANUFACTURER PART NUMBER") "RC0603FR-07560RL")
        (field (name "TOLERANCE") "1%")
      )
      (libsource (lib "sch_library") (part "560R"))
    )
    (comp (ref "R43")
      (value "560R")
      (footprint "R_0603")
      (fields
        (field (name "MANUFACTURER") "Yageo")
        (field (name "MANUFACTURER PART NUMBER") "RC0603FR-07560RL")
        (field (name "TOLERANCE") "1%")
      )
      (libsource (lib "sch_library") (part "560R"))
    )
    (comp (ref "R44")
      (value "10k")
      (footprint "R_0603")
      (description "RES SMD 10K OHM 1% 1/10W 0603")
      (fields
        (field (name "MANUFACTURER") "Yageo")
        (field (name "MANUFACTURER PART NUMBER") "AC0603FR-0710KL")
      )
      (libsource (lib "sch_library") (part "AC0603FR-0710KL"))
    )
    (comp (ref "R45")
      (value "10k")
      (footprint "R_0603")
      (description "RES SMD 10K OHM 1% 1/10W 0603")
      (fields
        (field (name "MANUFACTURER") "Yageo")
        (field (name "MANUFACTURER PART NUMBER") "AC0603FR-0710KL")
      )
      (libsource (lib "sch_library") (part "AC0603FR-0710KL"))
    )
    (comp (ref "R46")
      (value "10k")
      (footprint "R_0603")
      (description "RES SMD 10K OHM 1% 1/10W 0603")
      (fields
        (field (name "MANUFACTURER") "Yageo")
        (field (name "MANUFACTURER PART NUMBER") "AC0603FR-0710KL")
      )
      (libsource (lib "sch_library") (part "AC0603FR-0710KL"))
    )
    (comp (ref "R47")
      (value "22R")
      (footprint "R_0805")
      (description "RES SMD 22 OHM 1% 1/8W 0805")
      (fields
        (field (name "MANUFACTURER") "Yageo")
        (field (name "MANUFACTURER PART NUMBER") "RC0805FR-0722RL")
      )
      (libsource (lib "sch_library") (part "RC0805FR-0722RL"))
    )
    (comp (ref "R48")
      (value "22R")
      (footprint "R_0805")
      (description "RES SMD 22 OHM 1% 1/8W 0805")
      (fields
        (field (name "MANUFACTURER") "Yageo")
        (field (name "MANUFACTURER PART NUMBER") "RC0805FR-0722RL")
      )
      (libsource (lib "sch_library") (part "RC0805FR-0722RL"))
    )
    (comp (ref "R49")
      (value "560R")
      (footprint "R_0603")
      (fields
        (field (name "MANUFACTURER") "Yageo")
        (field (name "MANUFACTURER PART NUMBER") "RC0603FR-07560RL")
        (field (name "TOLERANCE") "1%")
      )
      (libsource (lib "sch_library") (part "560R"))
    )
    (comp (ref "SOCKET1")
      (value "4828-3004-CP")
      (description "CONN IC DIP SOCKET 28POS TIN")
      (fields (field (name "MANUFACTURER") "3M"))
      (libsource (lib "sch_library") (part "4828-3004-CP"))
    )
    (comp (ref "SW1")
      (value "1825910-6")
      (footprint "BUTTON")
      (description "SWITCH TACTILE SPST-NO 0.05A 24V")
      (fields (field (name "MANUFACTURER") "TE Connectivity Alcoswitch"))
      (libsource (lib "sch_library") (part "1825910-6"))
    )
    (comp (ref "U1")
      (value "LMR33610ADDAR")
      (footprint "HSOIC8")
      (description "SIMPLE SWITCHER Synchronous Step-Down Converter 3.8V to 36V Input 1A 8-Pin SO PowerPAD T/R")
      (fields
        (field (name "MANUFACTURER") "Texas Instruments")
        (field (name "SUPPLIER PART NUMBER 1") "296-LMR33610ADDARDKR-ND")
      )
      (libsource (lib "sch_library") (part "LMR33610ADDAR"))
    )
    (comp (ref "U2")
      (value "AS7805ADTR-G1")
      (footprint "TO-252")
      (description "Standard Regulator Pos 5V 1A 3-Pin(2+Tab) TO-252 T/R")
      (fields (field (name "MANUFACTURER") "Diodes"))
      (libsource (lib "sch_library") (part "AS7805ADTR-G1"))
    )
    (comp (ref "U3")
      (value "MCP9808-E/MS")
      (footprint "MCHP-MSOP-MS8_L")
      (fields (field (name "MANUFACTURER") "Microchip"))
      (libsource (lib "Altium Content Vault") (part "MCHP-MCP9808-MSOP-8"))
    )
    (comp (ref "U4")
      (value "LM1117MPX-3.3/NOPB")
      (footprint "DCY0004A_L")
      (description "800mA Low-Dropout Linear Regulator, 4-pin SOT-223, Pb-Free")
      (fields (field (name "MANUFACTURER") "Texas Instruments"))
      (libsource (lib "Altium Content Vault") (part "PM-REG-LM1086-SOT4"))
    )
    (comp (ref "U5")
      (value "ATMEGA16U2-AU")
      (footprint "TQFP32")
      (description "MICROCHIP - ATMEGA16U2-AU - MCU, 8BIT, MEGAAVR, 16MHZ, TQFP-32")
      (fields
        (field (name "MANUFACTURER") "Microchip / Atmel")
        (field (name "SUPPLIER PART NUMBER 1") "ATMEGA16U2-AU-ND")
      )
      (libsource (lib "sch_library") (part "ATMEGA16U2-AU"))
    )
    (comp (ref "U6")
      (value "raspberry_pi_connector")
      (footprint "raspberry_pi")
      (libsource (lib "sch_library") (part "raspberry_pi_connector"))
    )
    (comp (ref "U7")
      (value "ATMEGA328P-PU")
      (footprint "DIP28_7.62mm")
      (description "ATMEGA328P-PU; 8 bit Microcontroller AVR 20MHz 1; 32kb Flash; 2kb RAM; I2C SPI 2")
      (fields
        (field (name "MANUFACTURER") "Microchip / Atmel")
        (field (name "SUPPLIER PART NUMBER 1") "ATMEGA328P-PU-ND")
      )
      (libsource (lib "sch_library") (part "ATMEGA328P-PU"))
    )
    (comp (ref "U8")
      (value "74HC4050D,653")
      (footprint "FP-SOT109-1-MFG")
      (description "IC BUFFER NON-INVERT 6V 16SO")
      (libsource (lib "Altium Content Vault") (part "d97c46871731a19363ffc4a5766e355"))
    )
    (comp (ref "U9")
      (value "RFM95W-868S2")
      (footprint "RFM69HCW")
      (description "RF TXRX MODULE ISM<1GHZ")
      (fields (field (name "MANUFACTURER") "RF Solutions"))
      (libsource (lib "sch_library") (part "RFM95W-868S2"))
    )
    (comp (ref "U10")
      (value "SN74AHC1G09DBVR")
      (footprint "SOT-23")
      (description "TEXAS INSTRUMENTS - SN74AHC1G09DBVR - AND Gate, 74AHC1G09, 2 Input, 2 V to 5.5 V, SOT-23-5")
      (fields (field (name "MANUFACTURER") "Texas Instruments"))
      (libsource (lib "sch_library") (part "SN74AHC1G09DBVR"))
    )
    (comp (ref "U11")
      (value "SN74AHC1G09DBVR")
      (footprint "SOT-23")
      (description "TEXAS INSTRUMENTS - SN74AHC1G09DBVR - AND Gate, 74AHC1G09, 2 Input, 2 V to 5.5 V, SOT-23-5")
      (fields (field (name "MANUFACTURER") "Texas Instruments"))
      (libsource (lib "sch_library") (part "SN74AHC1G09DBVR"))
    )
    (comp (ref "U12")
      (value "SN74AHC1G09DBVR")
      (footprint "SOT-23")
      (description "TEXAS INSTRUMENTS - SN74AHC1G09DBVR - AND Gate, 74AHC1G09, 2 Input, 2 V to 5.5 V, SOT-23-5")
      (fields (field (name "MANUFACTURER") "Texas Instruments"))
      (libsource (lib "sch_library") (part "SN74AHC1G09DBVR"))
    )
    (comp (ref "Y1")
      (value "16MHz")
      (footprint "ABM7_v1_1_BIG")
      (description "CRYSTAL 16.0000MHZ 18PF SMD")
      (fields
        (field (name "MANUFACTURER") "Abracon")
        (field (name "MANUFACTURER PART NUMBER") "ABM7-16.000MHZ-D2Y-T")
      )
      (libsource (lib "sch_library") (part "ABM7-16.000MHZ-D2Y-T"))
    )
    (comp (ref "Y2")
      (value "CRYSTAL 16.0000MHZ 18PF SMD")
      (footprint "ABM7_v1_1_BIG")
      (fields
        (field (name "MANUFACTURER") "Abracon")
        (field (name "MANUFACTURER PART NUMBER") "ABM7-16.000MHZ-D2Y-T")
        (field (name "TOLERANCE") "20ppm")
      )
      (libsource (lib "sch_library") (part "ABM7-16.000MHZ-D2Y-T"))
    )
    (comp (ref "Z1")
      (value "CG0603MLC-05E")
      (footprint "CG0603MLC-05E")
      (description "VARISTOR 0603")
      (fields (field (name "MANUFACTURER") "Bourns") (field (name "VOLTAGE") "5V"))
      (libsource (lib "sch_library") (part "CG0603MLC-05E"))
    )
    (comp (ref "Z2")
      (value "CG0603MLC-05E")
      (footprint "CG0603MLC-05E")
      (description "VARISTOR 0603")
      (fields (field (name "MANUFACTURER") "Bourns") (field (name "VOLTAGE") "5V"))
      (libsource (lib "sch_library") (part "CG0603MLC-05E"))
    )
  )
  (nets
    (net (code "1") (name "+3V3") (class "Default")
      (node (ref "C13") (pin "1") (pinfunction "1_1") (pintype "passive"))
      (node (ref "C32") (pin "2") (pinfunction "2_2") (pintype "passive"))
      (node (ref "Q1") (pin "1") (pinfunction "G_1") (pintype "passive"))
      (node (ref "Q2") (pin "1") (pinfunction "G_1") (pintype "passive"))
      (node (ref "Q3") (pin "1") (pinfunction "G_1") (pintype "passive"))
      (node (ref "Q4") (pin "1") (pinfunction "G_1") (pintype "passive"))
      (node (ref "Q6") (pin "1") (pinfunction "G_1") (pintype "passive"))
      (node (ref "R10") (pin "2") (pinfunction "2_2") (pintype "passive"))
      (node (ref "R16") (pin "2") (pinfunction "2_2") (pintype "passive"))
      (node (ref "R19") (pin "2") (pinfunction "2_2") (pintype "passive"))
      (node (ref "R35") (pin "2") (pinfunction "2_2") (pintype "passive"))
      (node (ref "R42") (pin "1") (pinfunction "1_1") (pintype "passive"))
      (node (ref "R8") (pin "2") (pinfunction "2_2") (pintype "passive"))
      (node (ref "U4") (pin "2") (pinfunction "OUT_2") (pintype "power_in"))
      (node (ref "U4") (pin "4") (pinfunction "TAB_4") (pintype "power_in"))
      (node (ref "U8") (pin "1") (pinfunction "VCC_1") (pintype "power_in"))
      (node (ref "U9") (pin "13") (pinfunction "3.3V_13") (pintype "power_in"))
    )
    (net (code "2") (name "+5V") (class "Default")
      (node (ref "BUZZER1") (pin "1") (pinfunction "1_1") (pintype "passive"))
      (node (ref "C11") (pin "1") (pinfunction "1_1") (pintype "passive"))
      (node (ref "C12") (pin "1") (pinfunction "1_1") (pintype "passive"))
      (node (ref "C17") (pin "2") (pinfunction "2_2") (pintype "passive"))
      (node (ref "C33") (pin "1") (pinfunction "1_1") (pintype "passive"))
      (node (ref "C34") (pin "1") (pinfunction "1_1") (pintype "passive"))
      (node (ref "C35") (pin "2") (pinfunction "2_2") (pintype "passive"))
      (node (ref "D1") (pin "1") (pinfunction "1_1") (pintype "passive"))
      (node (ref "D2") (pin "1") (pinfunction "1_1") (pintype "passive"))
      (node (ref "FB1") (pin "1") (pinfunction "1_1") (pintype "passive"))
      (node (ref "FB2") (pin "1") (pinfunction "1_1") (pintype "passive"))
      (node (ref "FB3") (pin "1") (pinfunction "1_1") (pintype "passive"))
      (node (ref "J1") (pin "1") (pinfunction "1_1") (pintype "passive"))
      (node (ref "J17") (pin "1") (pinfunction "1_1") (pintype "passive"))
      (node (ref "J17") (pin "3") (pinfunction "3_3") (pintype "passive"))
      (node (ref "J17") (pin "5") (pinfunction "5_5") (pintype "passive"))
      (node (ref "J2") (pin "1") (pinfunction "1_1") (pintype "passive"))
      (node (ref "J21") (pin "2") (pinfunction "2_2") (pintype "passive"))
      (node (ref "J4") (pin "1") (pinfunction "1_1") (pintype "passive"))
      (node (ref "J54") (pin "1") (pinfunction "1_1") (pintype "passive"))
      (node (ref "R11") (pin "1") (pinfunction "1_1") (pintype "passive"))
      (node (ref "R12") (pin "1") (pinfunction "1_1") (pintype "passive"))
      (node (ref "R13") (pin "1") (pinfunction "1_1") (pintype "passive"))
      (node (ref "R14") (pin "2") (pinfunction "2_2") (pintype "passive"))
      (node (ref "R15") (pin "2") (pinfunction "2_2") (pintype "passive"))
      (node (ref "R18") (pin "2") (pinfunction "2_2") (pintype "passive"))
      (node (ref "R21") (pin "2") (pinfunction "2_2") (pintype "passive"))
      (node (ref "R26") (pin "2") (pinfunction "2_2") (pintype "passive"))
      (node (ref "R28") (pin "1") (pinfunction "1_1") (pintype "passive"))
      (node (ref "R30") (pin "1") (pinfunction "1_1") (pintype "passive"))
      (node (ref "R34") (pin "2") (pinfunction "2_2") (pintype "passive"))
      (node (ref "R36") (pin "2") (pinfunction "2_2") (pintype "passive"))
      (node (ref "R38") (pin "2") (pinfunction "2_2") (pintype "passive"))
      (node (ref "R39") (pin "2") (pinfunction "2_2") (pintype "passive"))
      (node (ref "R41") (pin "1") (pinfunction "1_1") (pintype "passive"))
      (node (ref "R43") (pin "2") (pinfunction "2_2") (pintype "passive"))
      (node (ref "R44") (pin "2") (pinfunction "2_2") (pintype "passive"))
      (node (ref "R45") (pin "2") (pinfunction "2_2") (pintype "passive"))
      (node (ref "R46") (pin "2") (pinfunction "2_2") (pintype "passive"))
      (node (ref "R49") (pin "1") (pinfunction "1_1") (pintype "passive"))
      (node (ref "R7") (pin "2") (pinfunction "2_2") (pintype "passive"))
      (node (ref "R9") (pin "2") (pinfunction "2_2") (pintype "passive"))
      (node (ref "U10") (pin "5") (pinfunction "5_5") (pintype "passive"))
      (node (ref "U11") (pin "5") (pinfunction "5_5") (pintype "passive"))
      (node (ref "U12") (pin "5") (pinfunction "5_5") (pintype "passive"))
      (node (ref "U3") (pin "8") (pinfunction "VDD_8") (pintype "power_in"))
      (node (ref "U4") (pin "3") (pinfunction "IN_3") (pintype "power_in"))
      (node (ref "U5") (pin "31") (pinfunction "UVCC_31") (pintype "passive"))
      (node (ref "U6") (pin "2") (pinfunction "5V_2") (pintype "passive"))
      (node (ref "U6") (pin "4") (pinfunction "5V_4") (pintype "passive"))
    )
    (net (code "3") (name "+5V_C") (class "Default")
      (node (ref "C19") (pin "1") (pinfunction "1_1") (pintype "passive"))
      (node (ref "J17") (pin "2") (pinfunction "2_2") (pintype "passive"))
      (node (ref "L2") (pin "2") (pinfunction "2_2") (pintype "passive"))
      (node (ref "R13") (pin "2") (pinfunction "2_2") (pintype "passive"))
    )
    (net (code "4") (name "+5V_LDO") (class "Default")
      (node (ref "C9") (pin "1") (pinfunction "1_1") (pintype "passive"))
      (node (ref "J17") (pin "4") (pinfunction "4_4") (pintype "passive"))
      (node (ref "R12") (pin "2") (pinfunction "2_2") (pintype "passive"))
      (node (ref "U2") (pin "3") (pinfunction "OUTPUT_3") (pintype "passive"))
    )
    (net (code "5") (name "+5V_SR") (class "Default")
      (node (ref "C4") (pin "1") (pinfunction "1_1") (pintype "passive"))
      (node (ref "C5") (pin "1") (pinfunction "1_1") (pintype "passive"))
      (node (ref "C6") (pin "1") (pinfunction "1_1") (pintype "passive"))
      (node (ref "C7") (pin "1") (pinfunction "1_1") (pintype "passive"))
      (node (ref "J17") (pin "6") (pinfunction "6_6") (pintype "passive"))
      (node (ref "L1") (pin "2") (pinfunction "2_2") (pintype "passive"))
      (node (ref "R11") (pin "2") (pinfunction "2_2") (pintype "passive"))
      (node (ref "R4") (pin "2") (pinfunction "2_2") (pintype "passive"))
      (node (ref "R5") (pin "2") (pinfunction "2_2") (pintype "passive"))
    )
    (net (code "6") (name "+AREF") (class "Default")
      (node (ref "C25") (pin "2") (pinfunction "2_2") (pintype "passive"))
      (node (ref "C28") (pin "2") (pinfunction "2_2") (pintype "passive"))
      (node (ref "U7") (pin "21") (pinfunction "AREF_21") (pintype "passive"))
    )
    (net (code "7") (name "/+3V3_16U2_UCAP") (class "Default")
      (node (ref "C20") (pin "2") (pinfunction "2_2") (pintype "passive"))
      (node (ref "U5") (pin "27") (pinfunction "UCAP_27") (pintype "passive"))
    )
    (net (code "8") (name "/+5V_USB") (class "Default")
      (node (ref "C18") (pin "1") (pinfunction "1_1") (pintype "passive"))
      (node (ref "J19") (pin "1") (pinfunction "1_1") (pintype "passive"))
      (node (ref "L2") (pin "1") (pinfunction "1_1") (pintype "passive"))
    )
    (net (code "9") (name "/+5V{slash}3V3_16U2") (class "Default")
      (node (ref "C14") (pin "2") (pinfunction "2_2") (pintype "passive"))
      (node (ref "C15") (pin "2") (pinfunction "2_2") (pintype "passive"))
      (node (ref "C16") (pin "2") (pinfunction "2_2") (pintype "passive"))
      (node (ref "FB1") (pin "2") (pinfunction "2_2") (pintype "passive"))
      (node (ref "U5") (pin "32") (pinfunction "AVCC_32") (pintype "passive"))
      (node (ref "U5") (pin "4") (pinfunction "VCC_4") (pintype "passive"))
    )
    (net (code "10") (name "/+5V{slash}3V3_328P_AVCC") (class "Default")
      (node (ref "C26") (pin "2") (pinfunction "2_2") (pintype "passive"))
      (node (ref "C27") (pin "2") (pinfunction "2_2") (pintype "passive"))
      (node (ref "FB3") (pin "2") (pinfunction "2_2") (pintype "passive"))
      (node (ref "U7") (pin "20") (pinfunction "AVCC_20") (pintype "passive"))
    )
    (net (code "11") (name "/+5V{slash}3V3_328P_VCC") (class "Default")
      (node (ref "C23") (pin "2") (pinfunction "2_2") (pintype "passive"))
      (node (ref "C24") (pin "2") (pinfunction "2_2") (pintype "passive"))
      (node (ref "FB2") (pin "2") (pinfunction "2_2") (pintype "passive"))
      (node (ref "U7") (pin "7") (pinfunction "VCC_7") (pintype "passive"))
    )
    (net (code "12") (name "/16U2PROG_328P_RESETn") (class "Default")
      (node (ref "J49") (pin "2") (pinfunction "2_2") (pintype "passive"))
      (node (ref "R21") (pin "1") (pinfunction "1_1") (pintype "passive"))
      (node (ref "U5") (pin "13") (pinfunction "/_HWB_/_AIN6_/_T0_/_INT7)_PD7_13") (pintype "passive"))
    )
    (net (code "13") (name "/16U2_16MHZ_XTAL1") (class "Default")
      (node (ref "C21") (pin "2") (pinfunction "2_2") (pintype "passive"))
      (node (ref "R23") (pin "2") (pinfunction "2_2") (pintype "passive"))
      (node (ref "U5") (pin "1") (pinfunction "XTAL1_1") (pintype "passive"))
      (node (ref "Y1") (pin "1") (pinfunction "1_1") (pintype "passive"))
    )
    (net (code "14") (name "/16U2_16MHZ_XTAL2") (class "Default")
      (node (ref "C22") (pin "2") (pinfunction "2_2") (pintype "passive"))
      (node (ref "R23") (pin "1") (pinfunction "1_1") (pintype "passive"))
      (node (ref "U5") (pin "2") (pinfunction "(PC0)_XTAL2_2") (pintype "passive"))
      (node (ref "Y1") (pin "2") (pinfunction "2_2") (pintype "passive"))
    )
    (net (code "15") (name "/16U2_BUF_RESETn") (class "Default")
      (node (ref "C37") (pin "2") (pinfunction "2_2") (pintype "passive"))
      (node (ref "R48") (pin "2") (pinfunction "2_2") (pintype "passive"))
      (node (ref "U11") (pin "1") (pinfunction "1_1") (pintype "passive"))
      (node (ref "U11") (pin "2") (pinfunction "2_2") (pintype "passive"))
    )
    (net (code "16") (name "/16U2_MISO") (class "Default")
      (node (ref "U5") (pin "16") (pinfunction "(PDI_/_MOSI_/_PCINT2)_PB2_16") (pintype "passive+no_connect"))
    )
    (net (code "17") (name "/16U2_MOSI") (class "Default")
      (node (ref "U5") (pin "17") (pinfunction "PB3_(PDO_/_MISO_/_PCINT3)_17") (pintype "passive+no_connect"))
    )
    (net (code "18") (name "/16U2_PB4") (class "Default")
      (node (ref "U5") (pin "18") (pinfunction "PB4_(T1_/_PCINT4)_18") (pintype "passive+no_connect"))
    )
    (net (code "19") (name "/16U2_PB5") (class "Default")
      (node (ref "U5") (pin "19") (pinfunction "PB5_(PCINT5)_19") (pintype "passive+no_connect"))
    )
    (net (code "20") (name "/16U2_PB6") (class "Default")
      (node (ref "U5") (pin "20") (pinfunction "PB6_(PCINT6)_20") (pintype "passive+no_connect"))
    )
    (net (code "21") (name "/16U2_PB7") (class "Default")
      (node (ref "U5") (pin "21") (pinfunction "PB7_(PCINT7_/_OC.0A_/_OC.1C)_21") (pintype "passive+no_connect"))
    )
    (net (code "22") (name "/16U2_RESETn") (class "Default")
      (node (ref "R14") (pin "1") (pinfunction "1_1") (pintype "passive"))
      (node (ref "U11") (pin "4") (pinfunction "4_4") (pintype "passive"))
      (node (ref "U5") (pin "24") (pinfunction "Reset_(PC1_/_dW)_24") (pintype "passive"))
    )
    (net (code "23") (name "/16U2_RX") (class "Default")
      (node (ref "R27") (pin "1") (pinfunction "1_1") (pintype "passive"))
      (node (ref "U5") (pin "8") (pinfunction "(RXD1_/_AIN1_/_INT2)_PD2_8") (pintype "passive"))
    )
    (net (code "24") (name "/16U2_RX_LED") (class "Default")
      (node (ref "LED1") (pin "1") (pinfunction "1_1") (pintype "passive"))
      (node (ref "U5") (pin "10") (pinfunction "(INT5/_AIN3)_PD4_10") (pintype "passive"))
    )
    (net (code "25") (name "/16U2_SCLK_R") (class "Default")
      (node (ref "U5") (pin "15") (pinfunction "(SCLK_/_PCINT1)_PB1_15") (pintype "passive+no_connect"))
    )
    (net (code "26") (name "/16U2_TX") (class "Default")
      (node (ref "R25") (pin "1") (pinfunction "1_1") (pintype "passive"))
      (node (ref "U5") (pin "9") (pinfunction "(TXD1_/_INT3)_PD3_9") (pintype "passive"))
    )
    (net (code "27") (name "/16U2_TX_LED") (class "Default")
      (node (ref "LED2") (pin "1") (pinfunction "1_1") (pintype "passive"))
      (node (ref "U5") (pin "11") (pinfunction "(XCK_AIN4_/_PCINT12)_PD5_11") (pintype "passive"))
    )
    (net (code "28") (name "/328P_16MHZ_XTAL1") (class "Default")
      (node (ref "C30") (pin "2") (pinfunction "2_2") (pintype "passive"))
      (node (ref "R37") (pin "1") (pinfunction "1_1") (pintype "passive"))
      (node (ref "U7") (pin "9") (pinfunction "(PCINT6/XTAL1/TOSC1)_PB6_9") (pintype "passive"))
      (node (ref "Y2") (pin "2") (pinfunction "2_2") (pintype "passive"))
    )
    (net (code "29") (name "/328P_16MHZ_XTAL2") (class "Default")
      (node (ref "C29") (pin "2") (pinfunction "2_2") (pintype "passive"))
      (node (ref "R37") (pin "2") (pinfunction "2_2") (pintype "passive"))
      (node (ref "U7") (pin "10") (pinfunction "(PCINT7/XTAL2/TOSC2)_PB7_10") (pintype "passive"))
      (node (ref "Y2") (pin "1") (pinfunction "1_1") (pintype "passive"))
    )
    (net (code "30") (name "/328P_AUTORESETn") (class "Default")
      (node (ref "C31") (pin "1") (pinfunction "1_1") (pintype "passive"))
      (node (ref "R44") (pin "1") (pinfunction "1_1") (pintype "passive"))
      (node (ref "U10") (pin "1") (pinfunction "1_1") (pintype "passive"))
    )
    (net (code "31") (name "/328P_BUF_RESETn") (class "Default")
      (node (ref "C36") (pin "2") (pinfunction "2_2") (pintype "passive"))
      (node (ref "R47") (pin "2") (pinfunction "2_2") (pintype "passive"))
      (node (ref "U10") (pin "2") (pinfunction "2_2") (pintype "passive"))
    )
    (net (code "32") (name "/328P_RESETn") (class "Default")
      (node (ref "R36") (pin "1") (pinfunction "1_1") (pintype "passive"))
      (node (ref "U10") (pin "4") (pinfunction "4_4") (pintype "passive"))
      (node (ref "U7") (pin "1") (pinfunction "(PCINT14/RESET)_PC6_1") (pintype "passive"))
    )
    (net (code "33") (name "/AD3") (class "Default")
      (node (ref "J30") (pin "1") (pinfunction "1_1") (pintype "passive"))
      (node (ref "U7") (pin "26") (pinfunction "PC3_(ADC3/PCINT11)_26") (pintype "passive"))
    )
    (net (code "34") (name "/BAT_MEASUREMENT") (class "Default")
      (node (ref "J31") (pin "1") (pinfunction "1_1") (pintype "passive"))
      (node (ref "R31") (pin "1") (pinfunction "1_1") (pintype "passive"))
      (node (ref "R32") (pin "2") (pinfunction "2_2") (pintype "passive"))
      (node (ref "U7") (pin "25") (pinfunction "PC2_(ADC2/PCINT10)_25") (pintype "passive"))
    )
    (net (code "35") (name "/BUTTON_RESETn") (class "Default")
      (node (ref "D1") (pin "2") (pinfunction "2_2") (pintype "passive"))
      (node (ref "R45") (pin "1") (pinfunction "1_1") (pintype "passive"))
      (node (ref "R47") (pin "1") (pinfunction "1_1") (pintype "passive"))
      (node (ref "SW1") (pin "3") (pinfunction "3_3") (pintype "passive"))
      (node (ref "SW1") (pin "4") (pinfunction "4_4") (pintype "passive"))
    )
    (net (code "36") (name "/BUZZER_PWM") (class "Default")
      (node (ref "J26") (pin "1") (pinfunction "1_1") (pintype "passive"))
      (node (ref "R29") (pin "1") (pinfunction "1_1") (pintype "passive"))
      (node (ref "U7") (pin "15") (pinfunction "PB1_(OC1A/PCINT1)_15") (pintype "passive"))
    )
    (net (code "37") (name "/CON_USB_N") (class "Default")
      (node (ref "J19") (pin "2") (pinfunction "2_2") (pintype "passive"))
      (node (ref "R20") (pin "1") (pinfunction "1_1") (pintype "passive"))
      (node (ref "Z2") (pin "2") (pinfunction "2_2") (pintype "passive"))
    )
    (net (code "38") (name "/CON_USB_P") (class "Default")
      (node (ref "J19") (pin "3") (pinfunction "3_3") (pintype "passive"))
      (node (ref "R22") (pin "1") (pinfunction "1_1") (pintype "passive"))
      (node (ref "Z1") (pin "2") (pinfunction "2_2") (pintype "passive"))
    )
    (net (code "39") (name "/IO7") (class "Default")
      (node (ref "J34") (pin "1") (pinfunction "1_1") (pintype "passive"))
      (node (ref "U7") (pin "13") (pinfunction "(PCINT23/AIN1)_PD7_13") (pintype "passive"))
    )
    (net (code "40") (name "/LED_OUT") (class "Default")
      (node (ref "J37") (pin "1") (pinfunction "1_1") (pintype "passive"))
      (node (ref "LED6") (pin "1") (pinfunction "1_1") (pintype "passive"))
      (node (ref "U7") (pin "11") (pinfunction "(PCINT21/OC0B/T1)_PD5_11") (pintype "passive"))
    )
    (net (code "41") (name "/MISO") (class "Default")
      (node (ref "J2") (pin "5") (pinfunction "5_5") (pintype "passive"))
      (node (ref "J23") (pin "1") (pinfunction "1_1") (pintype "passive"))
      (node (ref "Q6") (pin "3") (pinfunction "D_3") (pintype "passive"))
      (node (ref "R34") (pin "1") (pinfunction "1_1") (pintype "passive"))
      (node (ref "U7") (pin "18") (pinfunction "PB4_(MISO/PCINT4)_18") (pintype "passive"))
    )
    (net (code "42") (name "/MISO_3V3") (class "Default")
      (node (ref "Q6") (pin "2") (pinfunction "S_2") (pintype "passive"))
      (node (ref "R35") (pin "1") (pinfunction "1_1") (pintype "passive"))
      (node (ref "U9") (pin "2") (pinfunction "MISO_2") (pintype "input"))
    )
    (net (code "43") (name "/MOSI") (class "Default")
      (node (ref "J2") (pin "6") (pinfunction "6_6") (pintype "passive"))
      (node (ref "J24") (pin "1") (pinfunction "1_1") (pintype "passive"))
      (node (ref "U7") (pin "17") (pinfunction "PB3_(MOSI/OC2A/PCINT3)_17") (pintype "passive"))
      (node (ref "U8") (pin "3") (pinfunction "1A_3") (pintype "input"))
    )
    (net (code "44") (name "/MOSI_3V3") (class "Default")
      (node (ref "U8") (pin "2") (pinfunction "1Y_2") (pintype "output"))
      (node (ref "U9") (pin "3") (pinfunction "MOSI_3") (pintype "output"))
    )
    (net (code "45") (name "/PRESSURE_CS") (class "Default")
      (node (ref "J2") (pin "7") (pinfunction "7_7") (pintype "passive"))
      (node (ref "J25") (pin "1") (pinfunction "1_1") (pintype "passive"))
      (node (ref "U7") (pin "16") (pinfunction "PB2_(SS/OC1B/PCINT2)_16") (pintype "passive"))
    )
    (net (code "46") (name "/RF_CS") (class "Default")
      (node (ref "J27") (pin "1") (pinfunction "1_1") (pintype "passive"))
      (node (ref "R38") (pin "1") (pinfunction "1_1") (pintype "passive"))
      (node (ref "U7") (pin "14") (pinfunction "(PCINT0/CLKO/ICP1)_PB0_14") (pintype "passive"))
      (node (ref "U8") (pin "7") (pinfunction "3A_7") (pintype "input"))
    )
    (net (code "47") (name "/RF_CS_3V3") (class "Default")
      (node (ref "U8") (pin "6") (pinfunction "3Y_6") (pintype "output"))
      (node (ref "U9") (pin "5") (pinfunction "NSS_5") (pintype "input"))
    )
    (net (code "48") (name "/RF_RST") (class "Default")
      (node (ref "J39") (pin "1") (pinfunction "1_1") (pintype "passive"))
      (node (ref "R39") (pin "1") (pinfunction "1_1") (pintype "passive"))
      (node (ref "U7") (pin "6") (pinfunction "(PCINT20/XCK/T0)_PD4_6") (pintype "passive"))
      (node (ref "U8") (pin "9") (pinfunction "4A_9") (pintype "input"))
    )
    (net (code "49") (name "/RF_RST_3V3") (class "Default")
      (node (ref "U8") (pin "10") (pinfunction "4Y_10") (pintype "output"))
      (node (ref "U9") (pin "6") (pinfunction "RESET_6") (pintype "bidirectional"))
    )
    (net (code "50") (name "/RX") (class "Default")
      (node (ref "J52") (pin "1") (pinfunction "1_1") (pintype "passive"))
      (node (ref "R25") (pin "2") (pinfunction "2_2") (pintype "passive"))
      (node (ref "U7") (pin "2") (pinfunction "(PCINT16/RXD)_PD0_2") (pintype "passive"))
    )
    (net (code "51") (name "/RX2_3V3") (class "Default")
      (node (ref "Q4") (pin "2") (pinfunction "S_2") (pintype "passive"))
      (node (ref "R19") (pin "1") (pinfunction "1_1") (pintype "passive"))
      (node (ref "U6") (pin "10") (pinfunction "UART_RX_10") (pintype "passive"))
    )
    (net (code "52") (name "/RX2_5V") (class "Default")
      (node (ref "J43") (pin "1") (pinfunction "1_1") (pintype "passive"))
      (node (ref "Q3") (pin "3") (pinfunction "D_3") (pintype "passive"))
      (node (ref "R15") (pin "1") (pinfunction "1_1") (pintype "passive"))
      (node (ref "U7") (pin "4") (pinfunction "(PCINT18/INT0)_PD2_4") (pintype "passive"))
    )
    (net (code "53") (name "/SCL") (class "Default")
      (node (ref "J1") (pin "4") (pinfunction "4_4") (pintype "passive"))
      (node (ref "J28") (pin "1") (pinfunction "1_1") (pintype "passive"))
      (node (ref "J4") (pin "3") (pinfunction "3_3") (pintype "passive"))
      (node (ref "Q2") (pin "3") (pinfunction "D_3") (pintype "passive"))
      (node (ref "R9") (pin "1") (pinfunction "1_1") (pintype "passive"))
      (node (ref "U3") (pin "2") (pinfunction "SCL_2") (pintype "input"))
      (node (ref "U7") (pin "28") (pinfunction "PC5_(ADC5/SCL/PCINT13)_28") (pintype "passive"))
    )
    (net (code "54") (name "/SCLK") (class "Default")
      (node (ref "J2") (pin "4") (pinfunction "4_4") (pintype "passive"))
      (node (ref "J22") (pin "1") (pinfunction "1_1") (pintype "passive"))
      (node (ref "R33") (pin "2") (pinfunction "2_2") (pintype "passive"))
      (node (ref "U12") (pin "1") (pinfunction "1_1") (pintype "passive"))
      (node (ref "U12") (pin "2") (pinfunction "2_2") (pintype "passive"))
      (node (ref "U8") (pin "5") (pinfunction "2A_5") (pintype "input"))
    )
    (net (code "55") (name "/SCLK_3V3") (class "Default")
      (node (ref "U8") (pin "4") (pinfunction "2Y_4") (pintype "output"))
      (node (ref "U9") (pin "4") (pinfunction "SCK_4") (pintype "input"))
    )
    (net (code "56") (name "/SCLK_R") (class "Default")
      (node (ref "R33") (pin "1") (pinfunction "1_1") (pintype "passive"))
      (node (ref "U7") (pin "19") (pinfunction "PB5_(SCK/PCINT5)_19") (pintype "passive"))
    )
    (net (code "57") (name "/SCL_3V") (class "Default")
      (node (ref "Q2") (pin "2") (pinfunction "S_2") (pintype "passive"))
      (node (ref "R10") (pin "1") (pinfunction "1_1") (pintype "passive"))
    )
    (net (code "58") (name "/SDA") (class "Default")
      (node (ref "J1") (pin "5") (pinfunction "5_5") (pintype "passive"))
      (node (ref "J29") (pin "1") (pinfunction "1_1") (pintype "passive"))
      (node (ref "J4") (pin "4") (pinfunction "4_4") (pintype "passive"))
      (node (ref "Q1") (pin "3") (pinfunction "D_3") (pintype "passive"))
      (node (ref "R7") (pin "1") (pinfunction "1_1") (pintype "passive"))
      (node (ref "U3") (pin "1") (pinfunction "SDA_1") (pintype "bidirectional"))
      (node (ref "U7") (pin "27") (pinfunction "PC4_(ADC4/SDA/PCINT12)_27") (pintype "passive"))
    )
    (net (code "59") (name "/SDA_3V") (class "Default")
      (node (ref "Q1") (pin "2") (pinfunction "S_2") (pintype "passive"))
      (node (ref "R8") (pin "1") (pinfunction "1_1") (pintype "passive"))
    )
    (net (code "60") (name "/SERVO_PWM") (class "Default")
      (node (ref "J21") (pin "1") (pinfunction "1_1") (pintype "passive"))
      (node (ref "J35") (pin "1") (pinfunction "1_1") (pintype "passive"))
      (node (ref "U7") (pin "12") (pinfunction "(PCINT22/OC0A/AIN0)_PD6_12") (pintype "passive"))
    )
    (net (code "61") (name "/TMP_OUT") (class "Default")
      (node (ref "J18") (pin "4") (pinfunction "4_4") (pintype "passive"))
      (node (ref "J32") (pin "1") (pinfunction "1_1") (pintype "passive"))
      (node (ref "U7") (pin "24") (pinfunction "PC1_(ADC1/PCINT9)_24") (pintype "passive"))
    )
    (net (code "62") (name "/TX") (class "Default")
      (node (ref "J51") (pin "1") (pinfunction "1_1") (pintype "passive"))
      (node (ref "R27") (pin "2") (pinfunction "2_2") (pintype "passive"))
      (node (ref "U7") (pin "3") (pinfunction "(PCINT17/TXD)_PD1_3") (pintype "passive"))
    )
    (net (code "63") (name "/TX2_3V3") (class "Default")
      (node (ref "Q3") (pin "2") (pinfunction "S_2") (pintype "passive"))
      (node (ref "R16") (pin "1") (pinfunction "1_1") (pintype "passive"))
      (node (ref "U6") (pin "8") (pinfunction "UART_TX_8") (pintype "passive"))
    )
    (net (code "64") (name "/TX2_5V") (class "Default")
      (node (ref "J41") (pin "1") (pinfunction "1_1") (pintype "passive"))
      (node (ref "Q4") (pin "3") (pinfunction "D_3") (pintype "passive"))
      (node (ref "R18") (pin "1") (pinfunction "1_1") (pintype "passive"))
      (node (ref "U7") (pin "5") (pinfunction "(PCINT19/OC2B/INT1)_PD3_5") (pintype "passive"))
    )
    (net (code "65") (name "/USB_N") (class "Default")
      (node (ref "R20") (pin "2") (pinfunction "2_2") (pintype "passive"))
      (node (ref "U5") (pin "30") (pinfunction "D-_30") (pintype "passive"))
    )
    (net (code "66") (name "/USB_P") (class "Default")
      (node (ref "R22") (pin "2") (pinfunction "2_2") (pintype "passive"))
      (node (ref "U5") (pin "29") (pinfunction "D+_29") (pintype "passive"))
    )
    (net (code "67") (name "/WIND_OUT") (class "Default")
      (node (ref "J18") (pin "3") (pinfunction "3_3") (pintype "passive"))
      (node (ref "J33") (pin "1") (pinfunction "1_1") (pintype "passive"))
      (node (ref "U7") (pin "23") (pinfunction "PC0_(ADC0/PCINT8)_23") (pintype "passive"))
    )
    (net (code "68") (name "GND") (class "Default")
      (node (ref "C10") (pin "1") (pinfunction "1_1") (pintype "passive"))
      (node (ref "C11") (pin "2") (pinfunction "2_2") (pintype "passive"))
      (node (ref "C12") (pin "2") (pinfunction "2_2") (pintype "passive"))
      (node (ref "C13") (pin "2") (pinfunction "2_2") (pintype "passive"))
      (node (ref "C14") (pin "1") (pinfunction "1_1") (pintype "passive"))
      (node (ref "C15") (pin "1") (pinfunction "1_1") (pintype "passive"))
      (node (ref "C16") (pin "1") (pinfunction "1_1") (pintype "passive"))
      (node (ref "C17") (pin "1") (pinfunction "1_1") (pintype "passive"))
      (node (ref "C18") (pin "2") (pinfunction "2_2") (pintype "passive"))
      (node (ref "C19") (pin "2") (pinfunction "2_2") (pintype "passive"))
      (node (ref "C2") (pin "2") (pinfunction "2_2") (pintype "passive"))
      (node (ref "C20") (pin "1") (pinfunction "1_1") (pintype "passive"))
      (node (ref "C21") (pin "1") (pinfunction "1_1") (pintype "passive"))
      (node (ref "C22") (pin "1") (pinfunction "1_1") (pintype "passive"))
      (node (ref "C23") (pin "1") (pinfunction "1_1") (pintype "passive"))
      (node (ref "C24") (pin "1") (pinfunction "1_1") (pintype "passive"))
      (node (ref "C25") (pin "1") (pinfunction "1_1") (pintype "passive"))
      (node (ref "C26") (pin "1") (pinfunction "1_1") (pintype "passive"))
      (node (ref "C27") (pin "1") (pinfunction "1_1") (pintype "passive"))
      (node (ref "C28") (pin "1") (pinfunction "1_1") (pintype "passive"))
      (node (ref "C29") (pin "1") (pinfunction "1_1") (pintype "passive"))
      (node (ref "C3") (pin "2") (pinfunction "2_2") (pintype "passive"))
      (node (ref "C30") (pin "1") (pinfunction "1_1") (pintype "passive"))
      (node (ref "C32") (pin "1") (pinfunction "1_1") (pintype "passive"))
      (node (ref "C33") (pin "2") (pinfunction "2_2") (pintype "passive"))
      (node (ref "C34") (pin "2") (pinfunction "2_2") (pintype "passive"))
      (node (ref "C35") (pin "1") (pinfunction "1_1") (pintype "passive"))
      (node (ref "C36") (pin "1") (pinfunction "1_1") (pintype "passive"))
      (node (ref "C37") (pin "1") (pinfunction "1_1") (pintype "passive"))
      (node (ref "C4") (pin "2") (pinfunction "2_2") (pintype "passive"))
      (node (ref "C5") (pin "2") (pinfunction "2_2") (pintype "passive"))
      (node (ref "C6") (pin "2") (pinfunction "2_2") (pintype "passive"))
      (node (ref "C8") (pin "2") (pinfunction "2_2") (pintype "passive"))
      (node (ref "C9") (pin "2") (pinfunction "2_2") (pintype "passive"))
      (node (ref "J1") (pin "3") (pinfunction "3_3") (pintype "passive"))
      (node (ref "J18") (pin "1") (pinfunction "1_1") (pintype "passive"))
      (node (ref "J19") (pin "10") (pinfunction "10_10") (pintype "passive"))
      (node (ref "J19") (pin "11") (pinfunction "11_11") (pintype "passive"))
      (node (ref "J19") (pin "5") (pinfunction "5_5") (pintype "passive"))
      (node (ref "J19") (pin "6") (pinfunction "6_6") (pintype "passive"))
      (node (ref "J19") (pin "7") (pinfunction "7_7") (pintype "passive"))
      (node (ref "J19") (pin "8") (pinfunction "8_8") (pintype "passive"))
      (node (ref "J19") (pin "9") (pinfunction "9_9") (pintype "passive"))
      (node (ref "J2") (pin "3") (pinfunction "3_3") (pintype "passive"))
      (node (ref "J21") (pin "3") (pinfunction "3_3") (pintype "passive"))
      (node (ref "J4") (pin "2") (pinfunction "2_2") (pintype "passive"))
      (node (ref "J50") (pin "2") (pinfunction "2_2") (pintype "passive"))
      (node (ref "J50") (pin "3") (pinfunction "3_3") (pintype "passive"))
      (node (ref "J50") (pin "4") (pinfunction "4_4") (pintype "passive"))
      (node (ref "J50") (pin "5") (pinfunction "5_5") (pintype "passive"))
      (node (ref "J53") (pin "1") (pinfunction "1_1") (pintype "passive"))
      (node (ref "LED3") (pin "1") (pinfunction "1_1") (pintype "passive"))
      (node (ref "LED4") (pin "1") (pinfunction "1_1") (pintype "passive"))
      (node (ref "P1") (pin "2") (pinfunction "2_2") (pintype "passive"))
      (node (ref "Q5") (pin "1") (pinfunction "E_1") (pintype "passive"))
      (node (ref "R1") (pin "2") (pinfunction "2_2") (pintype "passive"))
      (node (ref "R2") (pin "2") (pinfunction "2_2") (pintype "passive"))
      (node (ref "R24") (pin "2") (pinfunction "2_2") (pintype "passive"))
      (node (ref "R3") (pin "1") (pinfunction "1_1") (pintype "passive"))
      (node (ref "R32") (pin "1") (pinfunction "1_1") (pintype "passive"))
      (node (ref "R40") (pin "1") (pinfunction "1_1") (pintype "passive"))
      (node (ref "R6") (pin "1") (pinfunction "1_1") (pintype "passive"))
      (node (ref "SW1") (pin "1") (pinfunction "1_1") (pintype "passive"))
      (node (ref "SW1") (pin "2") (pinfunction "2_2") (pintype "passive"))
      (node (ref "U1") (pin "1") (pinfunction "PGND_1") (pintype "passive"))
      (node (ref "U1") (pin "9") (pinfunction "AGND_9") (pintype "passive"))
      (node (ref "U10") (pin "3") (pinfunction "3_3") (pintype "passive"))
      (node (ref "U11") (pin "3") (pinfunction "3_3") (pintype "passive"))
      (node (ref "U12") (pin "3") (pinfunction "3_3") (pintype "passive"))
      (node (ref "U2") (pin "2") (pinfunction "GND_2") (pintype "passive"))
      (node (ref "U3") (pin "4") (pinfunction "GND_4") (pintype "power_in"))
      (node (ref "U4") (pin "1") (pinfunction "GND_1") (pintype "power_in"))
      (node (ref "U5") (pin "28") (pinfunction "UGND_28") (pintype "passive"))
      (node (ref "U5") (pin "3") (pinfunction "GND_3") (pintype "passive"))
      (node (ref "U6") (pin "14") (pinfunction "GND_14") (pintype "passive"))
      (node (ref "U6") (pin "20") (pinfunction "GND_20") (pintype "passive"))
      (node (ref "U6") (pin "25") (pinfunction "GND_25") (pintype "passive"))
      (node (ref "U6") (pin "30") (pinfunction "GND_30") (pintype "passive"))
      (node (ref "U6") (pin "34") (pinfunction "GND_34") (pintype "passive"))
      (node (ref "U6") (pin "39") (pinfunction "GND_39") (pintype "passive"))
      (node (ref "U6") (pin "6") (pinfunction "GND_6") (pintype "passive"))
      (node (ref "U6") (pin "9") (pinfunction "GND_9") (pintype "passive"))
      (node (ref "U7") (pin "22") (pinfunction "GND_22") (pintype "passive"))
      (node (ref "U7") (pin "8") (pinfunction "GND_8") (pintype "passive"))
      (node (ref "U8") (pin "8") (pinfunction "GND_8") (pintype "power_in"))
      (node (ref "U9") (pin "1") (pinfunction "GND_1") (pintype "power_in"))
      (node (ref "U9") (pin "10") (pinfunction "GND_10") (pintype "power_in"))
      (node (ref "U9") (pin "8") (pinfunction "GND_8") (pintype "power_in"))
      (node (ref "Z1") (pin "1") (pinfunction "1_1") (pintype "passive"))
      (node (ref "Z2") (pin "1") (pinfunction "1_1") (pintype "passive"))
    )
    (net (code "69") (name "Net-(C31-Pad2)") (class "Default")
      (node (ref "C31") (pin "2") (pinfunction "2_2") (pintype "passive"))
      (node (ref "J49") (pin "1") (pinfunction "1_1") (pintype "passive"))
    )
    (net (code "70") (name "Net-(D2-Pad2)") (class "Default")
      (node (ref "D2") (pin "2") (pinfunction "2_2") (pintype "passive"))
      (node (ref "R46") (pin "1") (pinfunction "1_1") (pintype "passive"))
      (node (ref "R48") (pin "1") (pinfunction "1_1") (pintype "passive"))
    )
    (net (code "71") (name "Net-(J18-Pad5)") (class "Default")
      (node (ref "J18") (pin "5") (pinfunction "5_5") (pintype "passive"))
      (node (ref "J20") (pin "1") (pinfunction "1_1") (pintype "passive"))
    )
    (net (code "72") (name "Net-(J19-Pad4)") (class "Default")
      (node (ref "J19") (pin "4") (pinfunction "4_4") (pintype "passive"))
      (node (ref "R24") (pin "1") (pinfunction "1_1") (pintype "passive"))
    )
    (net (code "73") (name "Net-(J49-Pad3)") (class "Default")
      (node (ref "J49") (pin "3") (pinfunction "3_3") (pintype "passive"))
      (node (ref "R40") (pin "2") (pinfunction "2_2") (pintype "passive"))
    )
    (net (code "74") (name "Net-(LED1-Pad2)") (class "Default")
      (node (ref "LED1") (pin "2") (pinfunction "2_2") (pintype "passive"))
      (node (ref "R28") (pin "2") (pinfunction "2_2") (pintype "passive"))
    )
    (net (code "75") (name "Net-(LED2-Pad2)") (class "Default")
      (node (ref "LED2") (pin "2") (pinfunction "2_2") (pintype "passive"))
      (node (ref "R30") (pin "2") (pinfunction "2_2") (pintype "passive"))
    )
    (net (code "76") (name "Net-(LED3-Pad2)") (class "Default")
      (node (ref "LED3") (pin "2") (pinfunction "2_2") (pintype "passive"))
      (node (ref "R41") (pin "2") (pinfunction "2_2") (pintype "passive"))
    )
    (net (code "77") (name "Net-(LED4-Pad2)") (class "Default")
      (node (ref "LED4") (pin "2") (pinfunction "2_2") (pintype "passive"))
      (node (ref "R42") (pin "2") (pinfunction "2_2") (pintype "passive"))
    )
    (net (code "78") (name "Net-(LED5-Pad1)") (class "Default")
      (node (ref "LED5") (pin "1") (pinfunction "1_1") (pintype "passive"))
      (node (ref "U12") (pin "4") (pinfunction "4_4") (pintype "passive"))
    )
    (net (code "79") (name "Net-(LED5-Pad2)") (class "Default")
      (node (ref "LED5") (pin "2") (pinfunction "2_2") (pintype "passive"))
      (node (ref "R43") (pin "1") (pinfunction "1_1") (pintype "passive"))
    )
    (net (code "80") (name "Net-(LED6-Pad2)") (class "Default")
      (node (ref "LED6") (pin "2") (pinfunction "2_2") (pintype "passive"))
      (node (ref "R49") (pin "2") (pinfunction "2_2") (pintype "passive"))
    )
    (net (code "81") (name "Net-(Q5-B)") (class "Default")
      (node (ref "Q5") (pin "2") (pinfunction "B_2") (pintype "passive"))
      (node (ref "R29") (pin "2") (pinfunction "2_2") (pintype "passive"))
    )
    (net (code "82") (name "Net-(Q5-C)") (class "Default")
      (node (ref "BUZZER1") (pin "2") (pinfunction "2_2") (pintype "passive"))
      (node (ref "Q5") (pin "3") (pinfunction "C_3") (pintype "passive"))
      (node (ref "R26") (pin "1") (pinfunction "1_1") (pintype "passive"))
    )
    (net (code "83") (name "Net-(U1-BOOT)") (class "Default")
      (node (ref "C1") (pin "2") (pinfunction "2_2") (pintype "passive"))
      (node (ref "U1") (pin "7") (pinfunction "BOOT_7") (pintype "passive"))
    )
    (net (code "84") (name "Net-(U1-FB)") (class "Default")
      (node (ref "C7") (pin "2") (pinfunction "2_2") (pintype "passive"))
      (node (ref "R5") (pin "1") (pinfunction "1_1") (pintype "passive"))
      (node (ref "R6") (pin "2") (pinfunction "2_2") (pintype "passive"))
      (node (ref "U1") (pin "5") (pinfunction "FB_5") (pintype "passive"))
    )
    (net (code "85") (name "Net-(U1-PG)") (class "Default")
      (node (ref "R4") (pin "1") (pinfunction "1_1") (pintype "passive"))
      (node (ref "U1") (pin "4") (pinfunction "PG_4") (pintype "passive"))
    )
    (net (code "86") (name "Net-(U1-SW)") (class "Default")
      (node (ref "C1") (pin "1") (pinfunction "1_1") (pintype "passive"))
      (node (ref "L1") (pin "1") (pinfunction "1_1") (pintype "passive"))
      (node (ref "U1") (pin "8") (pinfunction "SW_8") (pintype "passive"))
    )
    (net (code "87") (name "Net-(U1-VCC)") (class "Default")
      (node (ref "C10") (pin "2") (pinfunction "2_2") (pintype "passive"))
      (node (ref "U1") (pin "6") (pinfunction "VCC_6") (pintype "passive"))
    )
    (net (code "88") (name "Net-(U3-A0)") (class "Default")
      (node (ref "R1") (pin "1") (pinfunction "1_1") (pintype "passive"))
      (node (ref "U3") (pin "7") (pinfunction "A0_7") (pintype "input"))
    )
    (net (code "89") (name "Net-(U3-A1)") (class "Default")
      (node (ref "R2") (pin "1") (pinfunction "1_1") (pintype "passive"))
      (node (ref "U3") (pin "6") (pinfunction "A1_6") (pintype "input"))
    )
    (net (code "90") (name "Net-(U3-A2)") (class "Default")
      (node (ref "R3") (pin "2") (pinfunction "2_2") (pintype "passive"))
      (node (ref "U3") (pin "5") (pinfunction "A2_5") (pintype "input"))
    )
    (net (code "91") (name "Net-(U9-ANT)") (class "Default")
      (node (ref "J48") (pin "1") (pinfunction "1_1") (pintype "passive"))
      (node (ref "J50") (pin "1") (pinfunction "1_1") (pintype "passive"))
      (node (ref "U9") (pin "9") (pinfunction "ANT_9") (pintype "bidirectional"))
    )
    (net (code "92") (name "VBAT") (class "Default")
      (node (ref "C2") (pin "1") (pinfunction "1_1") (pintype "passive"))
      (node (ref "C3") (pin "1") (pinfunction "1_1") (pintype "passive"))
      (node (ref "C8") (pin "1") (pinfunction "1_1") (pintype "passive"))
      (node (ref "J18") (pin "2") (pinfunction "2_2") (pintype "passive"))
      (node (ref "P1") (pin "1") (pinfunction "1_1") (pintype "passive"))
      (node (ref "R31") (pin "2") (pinfunction "2_2") (pintype "passive"))
      (node (ref "U1") (pin "2") (pinfunction "VIN_2") (pintype "passive"))
      (node (ref "U1") (pin "3") (pinfunction "EN_3") (pintype "passive"))
      (node (ref "U2") (pin "1") (pinfunction "INPUT_1") (pintype "passive"))
    )
    (net (code "93") (name "unconnected-(J1-Pad2)") (class "Default")
      (node (ref "J1") (pin "2") (pinfunction "2_2") (pintype "passive+no_connect"))
    )
    (net (code "94") (name "unconnected-(J1-Pad6)") (class "Default")
      (node (ref "J1") (pin "6") (pinfunction "6_6") (pintype "passive+no_connect"))
    )
    (net (code "95") (name "unconnected-(J1-Pad7)") (class "Default")
      (node (ref "J1") (pin "7") (pinfunction "7_7") (pintype "passive+no_connect"))
    )
    (net (code "96") (name "unconnected-(J1-Pad8)") (class "Default")
      (node (ref "J1") (pin "8") (pinfunction "8_8") (pintype "passive+no_connect"))
    )
    (net (code "97") (name "unconnected-(J1-Pad9)") (class "Default")
      (node (ref "J1") (pin "9") (pinfunction "9_9") (pintype "passive+no_connect"))
    )
    (net (code "98") (name "unconnected-(J2-Pad2)") (class "Default")
      (node (ref "J2") (pin "2") (pinfunction "2_2") (pintype "passive+no_connect"))
    )
    (net (code "99") (name "unconnected-(J2-Pad8)") (class "Default")
      (node (ref "J2") (pin "8") (pinfunction "8_8") (pintype "passive+no_connect"))
    )
    (net (code "100") (name "unconnected-(J4-Pad5)") (class "Default")
      (node (ref "J4") (pin "5") (pinfunction "5_5") (pintype "passive+no_connect"))
    )
    (net (code "101") (name "unconnected-(J4-Pad6)") (class "Default")
      (node (ref "J4") (pin "6") (pinfunction "6_6") (pintype "passive+no_connect"))
    )
    (net (code "102") (name "unconnected-(J4-Pad7)") (class "Default")
      (node (ref "J4") (pin "7") (pinfunction "7_7") (pintype "passive+no_connect"))
    )
    (net (code "103") (name "unconnected-(J4-Pad8)") (class "Default")
      (node (ref "J4") (pin "8") (pinfunction "8_8") (pintype "passive+no_connect"))
    )
    (net (code "104") (name "unconnected-(U3-ALERT-Pad3)") (class "Default")
      (node (ref "U3") (pin "3") (pinfunction "ALERT_3") (pintype "open_collector+no_connect"))
    )
    (net (code "105") (name "unconnected-(U5-(AIN0_{slash}_INT1)_PD1-Pad7)") (class "Default")
      (node (ref "U5") (pin "7") (pinfunction "(AIN0_/_INT1)_PD1_7") (pintype "passive+no_connect"))
    )
    (net (code "106") (name "unconnected-(U5-(OC.0B_{slash}_INT0)_PD0-Pad6)") (class "Default")
      (node (ref "U5") (pin "6") (pinfunction "(OC.0B_/_INT0)_PD0_6") (pintype "passive+no_connect"))
    )
    (net (code "107") (name "unconnected-(U5-(PCINT11_{slash}AIN2_)_PC2-Pad5)") (class "Default")
      (node (ref "U5") (pin "5") (pinfunction "(PCINT11_/AIN2_)_PC2_5") (pintype "passive+no_connect"))
    )
    (net (code "108") (name "unconnected-(U5-(RTS_{slash}_AIN5_{slash}_INT6)_PD6-Pad12)") (class "Default")
      (node (ref "U5") (pin "12") (pinfunction "(RTS_/_AIN5_/_INT6)_PD6_12") (pintype "passive+no_connect"))
    )
    (net (code "109") (name "unconnected-(U5-(SS_{slash}_PCINT0)_PB0-Pad14)") (class "Default")
      (node (ref "U5") (pin "14") (pinfunction "(SS_/_PCINT0)_PB0_14") (pintype "passive+no_connect"))
    )
    (net (code "110") (name "unconnected-(U5-PC4_(PCINT10)-Pad26)") (class "Default")
      (node (ref "U5") (pin "26") (pinfunction "PC4_(PCINT10)_26") (pintype "passive+no_connect"))
    )
    (net (code "111") (name "unconnected-(U5-PC5_(_PCINT9{slash}_OC.1B)-Pad25)") (class "Default")
      (node (ref "U5") (pin "25") (pinfunction "PC5_(_PCINT9/_OC.1B)_25") (pintype "passive+no_connect"))
    )
    (net (code "112") (name "unconnected-(U5-PC6_(OC.1A_{slash}_PCINT8)-Pad23)") (class "Default")
      (node (ref "U5") (pin "23") (pinfunction "PC6_(OC.1A_/_PCINT8)_23") (pintype "passive+no_connect"))
    )
    (net (code "113") (name "unconnected-(U5-PC7_(INT4_{slash}_ICP1_{slash}_CLKO)-Pad22)") (class "Default")
      (node (ref "U5") (pin "22") (pinfunction "PC7_(INT4_/_ICP1_/_CLKO)_22") (pintype "passive+no_connect"))
    )
    (net (code "114") (name "unconnected-(U6-3V3-Pad1)") (class "Default")
      (node (ref "U6") (pin "1") (pinfunction "3V3_1") (pintype "passive+no_connect"))
    )
    (net (code "115") (name "unconnected-(U6-3V3-Pad17)") (class "Default")
      (node (ref "U6") (pin "17") (pinfunction "3V3_17") (pintype "passive+no_connect"))
    )
    (net (code "116") (name "unconnected-(U6-GPIO4-Pad7)") (class "Default")
      (node (ref "U6") (pin "7") (pinfunction "GPIO4_7") (pintype "passive+no_connect"))
    )
    (net (code "117") (name "unconnected-(U6-GPIO5-Pad29)") (class "Default")
      (node (ref "U6") (pin "29") (pinfunction "GPIO5_29") (pintype "passive+no_connect"))
    )
    (net (code "118") (name "unconnected-(U6-GPIO6-Pad31)") (class "Default")
      (node (ref "U6") (pin "31") (pinfunction "GPIO6_31") (pintype "passive+no_connect"))
    )
    (net (code "119") (name "unconnected-(U6-GPIO7-Pad26)") (class "Default")
      (node (ref "U6") (pin "26") (pinfunction "GPIO7_26") (pintype "passive+no_connect"))
    )
    (net (code "120") (name "unconnected-(U6-GPIO8-Pad24)") (class "Default")
      (node (ref "U6") (pin "24") (pinfunction "GPIO8_24") (pintype "passive+no_connect"))
    )
    (net (code "121") (name "unconnected-(U6-GPIO12-Pad32)") (class "Default")
      (node (ref "U6") (pin "32") (pinfunction "GPIO12_32") (pintype "passive+no_connect"))
    )
    (net (code "122") (name "unconnected-(U6-GPIO13-Pad33)") (class "Default")
      (node (ref "U6") (pin "33") (pinfunction "GPIO13_33") (pintype "passive+no_connect"))
    )
    (net (code "123") (name "unconnected-(U6-GPIO16-Pad36)") (class "Default")
      (node (ref "U6") (pin "36") (pinfunction "GPIO16_36") (pintype "passive+no_connect"))
    )
    (net (code "124") (name "unconnected-(U6-GPIO17-Pad11)") (class "Default")
      (node (ref "U6") (pin "11") (pinfunction "GPIO17_11") (pintype "passive+no_connect"))
    )
    (net (code "125") (name "unconnected-(U6-GPIO19-Pad35)") (class "Default")
      (node (ref "U6") (pin "35") (pinfunction "GPIO19_35") (pintype "passive+no_connect"))
    )
    (net (code "126") (name "unconnected-(U6-GPIO20-Pad38)") (class "Default")
      (node (ref "U6") (pin "38") (pinfunction "GPIO20_38") (pintype "passive+no_connect"))
    )
    (net (code "127") (name "unconnected-(U6-GPIO21-Pad40)") (class "Default")
      (node (ref "U6") (pin "40") (pinfunction "GPIO21_40") (pintype "passive+no_connect"))
    )
    (net (code "128") (name "unconnected-(U6-GPIO22-Pad15)") (class "Default")
      (node (ref "U6") (pin "15") (pinfunction "GPIO22_15") (pintype "passive+no_connect"))
    )
    (net (code "129") (name "unconnected-(U6-GPIO23-Pad16)") (class "Default")
      (node (ref "U6") (pin "16") (pinfunction "GPIO23_16") (pintype "passive+no_connect"))
    )
    (net (code "130") (name "unconnected-(U6-GPIO24-Pad18)") (class "Default")
      (node (ref "U6") (pin "18") (pinfunction "GPIO24_18") (pintype "passive+no_connect"))
    )
    (net (code "131") (name "unconnected-(U6-GPIO25-Pad22)") (class "Default")
      (node (ref "U6") (pin "22") (pinfunction "GPIO25_22") (pintype "passive+no_connect"))
    )
    (net (code "132") (name "unconnected-(U6-GPIO26-Pad37)") (class "Default")
      (node (ref "U6") (pin "37") (pinfunction "GPIO26_37") (pintype "passive+no_connect"))
    )
    (net (code "133") (name "unconnected-(U6-GPIO27-Pad13)") (class "Default")
      (node (ref "U6") (pin "13") (pinfunction "GPIO27_13") (pintype "passive+no_connect"))
    )
    (net (code "134") (name "unconnected-(U6-ID_SC-Pad28)") (class "Default")
      (node (ref "U6") (pin "28") (pinfunction "ID_SC_28") (pintype "passive+no_connect"))
    )
    (net (code "135") (name "unconnected-(U6-ID_SD-Pad27)") (class "Default")
      (node (ref "U6") (pin "27") (pinfunction "ID_SD_27") (pintype "passive+no_connect"))
    )
    (net (code "136") (name "unconnected-(U6-MISO-Pad21)") (class "Default")
      (node (ref "U6") (pin "21") (pinfunction "MISO_21") (pintype "passive+no_connect"))
    )
    (net (code "137") (name "unconnected-(U6-MOSI-Pad19)") (class "Default")
      (node (ref "U6") (pin "19") (pinfunction "MOSI_19") (pintype "passive+no_connect"))
    )
    (net (code "138") (name "unconnected-(U6-PCM_CLK-Pad12)") (class "Default")
      (node (ref "U6") (pin "12") (pinfunction "PCM_CLK_12") (pintype "passive+no_connect"))
    )
    (net (code "139") (name "unconnected-(U6-SCL-Pad5)") (class "Default")
      (node (ref "U6") (pin "5") (pinfunction "SCL_5") (pintype "passive+no_connect"))
    )
    (net (code "140") (name "unconnected-(U6-SCLK-Pad23)") (class "Default")
      (node (ref "U6") (pin "23") (pinfunction "SCLK_23") (pintype "passive+no_connect"))
    )
    (net (code "141") (name "unconnected-(U6-SDA-Pad3)") (class "Default")
      (node (ref "U6") (pin "3") (pinfunction "SDA_3") (pintype "passive+no_connect"))
    )
    (net (code "142") (name "unconnected-(U8-5A-Pad11)") (class "Default")
      (node (ref "U8") (pin "11") (pinfunction "5A_11") (pintype "input+no_connect"))
    )
    (net (code "143") (name "unconnected-(U8-5Y-Pad12)") (class "Default")
      (node (ref "U8") (pin "12") (pinfunction "5Y_12") (pintype "output+no_connect"))
    )
    (net (code "144") (name "unconnected-(U8-6A-Pad14)") (class "Default")
      (node (ref "U8") (pin "14") (pinfunction "6A_14") (pintype "input+no_connect"))
    )
    (net (code "145") (name "unconnected-(U8-6Y-Pad15)") (class "Default")
      (node (ref "U8") (pin "15") (pinfunction "6Y_15") (pintype "output+no_connect"))
    )
    (net (code "146") (name "unconnected-(U8-NC-Pad13)") (class "Default")
      (node (ref "U8") (pin "13") (pinfunction "NC_13") (pintype "passive+no_connect"))
    )
    (net (code "147") (name "unconnected-(U8-NC-Pad16)") (class "Default")
      (node (ref "U8") (pin "16") (pinfunction "NC_16") (pintype "passive+no_connect"))
    )
    (net (code "148") (name "unconnected-(U9-DIO0-Pad14)") (class "Default")
      (node (ref "U9") (pin "14") (pinfunction "DIO0_14") (pintype "bidirectional+no_connect"))
    )
    (net (code "149") (name "unconnected-(U9-DIO1-Pad15)") (class "Default")
      (node (ref "U9") (pin "15") (pinfunction "DIO1_15") (pintype "bidirectional+no_connect"))
    )
    (net (code "150") (name "unconnected-(U9-DIO2-Pad16)") (class "Default")
      (node (ref "U9") (pin "16") (pinfunction "DIO2_16") (pintype "bidirectional+no_connect"))
    )
    (net (code "151") (name "unconnected-(U9-DIO3-Pad11)") (class "Default")
      (node (ref "U9") (pin "11") (pinfunction "DIO3_11") (pintype "bidirectional+no_connect"))
    )
    (net (code "152") (name "unconnected-(U9-DIO4-Pad12)") (class "Default")
      (node (ref "U9") (pin "12") (pinfunction "DIO4_12") (pintype "bidirectional+no_connect"))
    )
    (net (code "153") (name "unconnected-(U9-DIO5-Pad7)") (class "Default")
      (node (ref "U9") (pin "7") (pinfunction "DIO5_7") (pintype "bidirectional+no_connect"))
    )
  )
)
